# AtoVproject_16n_ALPS_V1_2NL.net
KiCad netlist of a schematic drawn in EAGLE
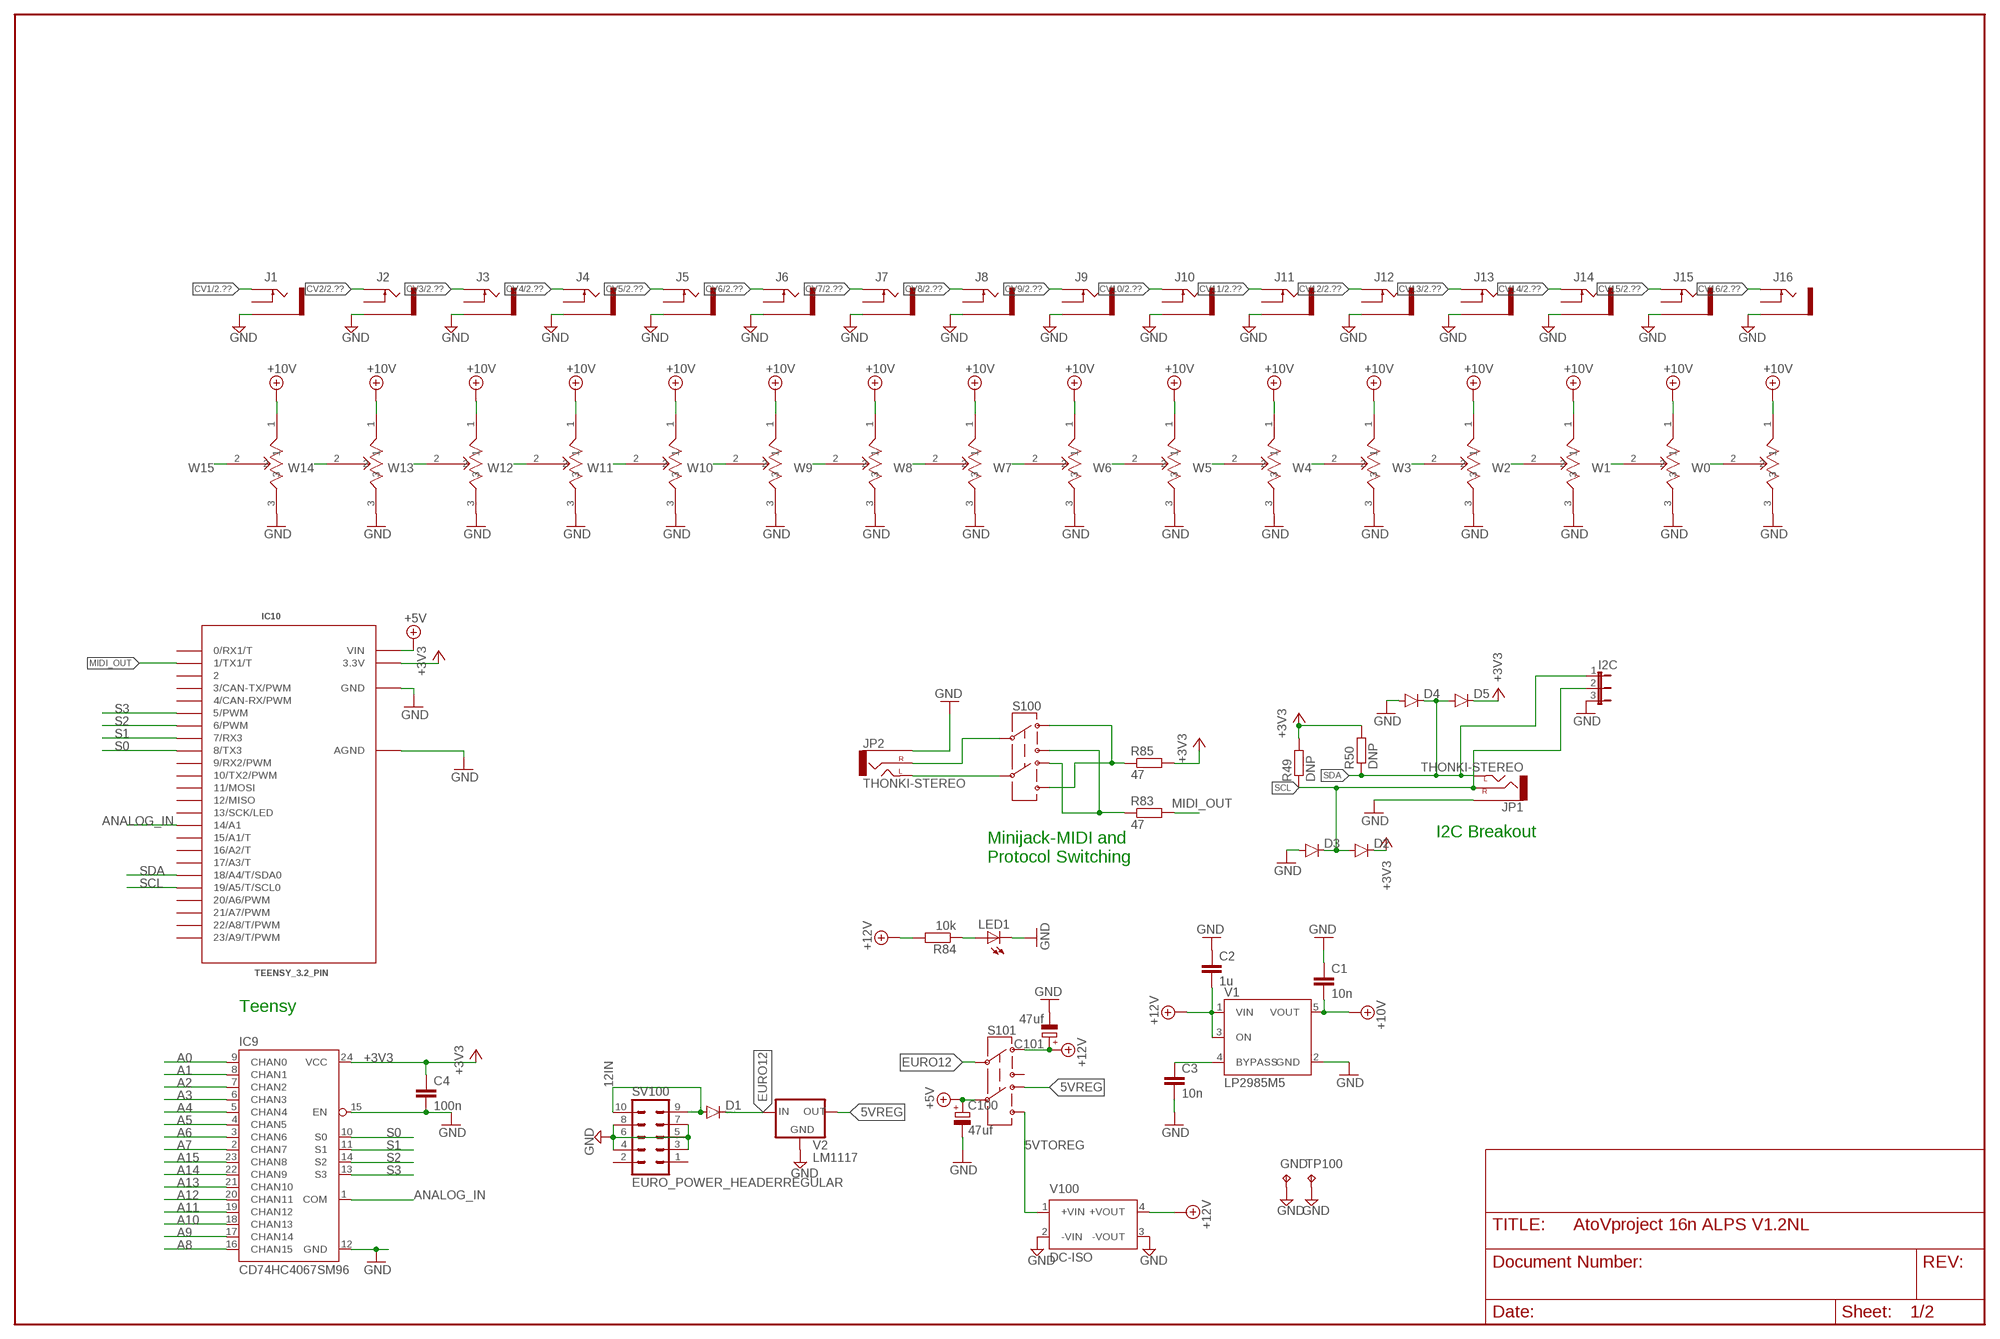
[diagram p0: schematic, sheet 1]
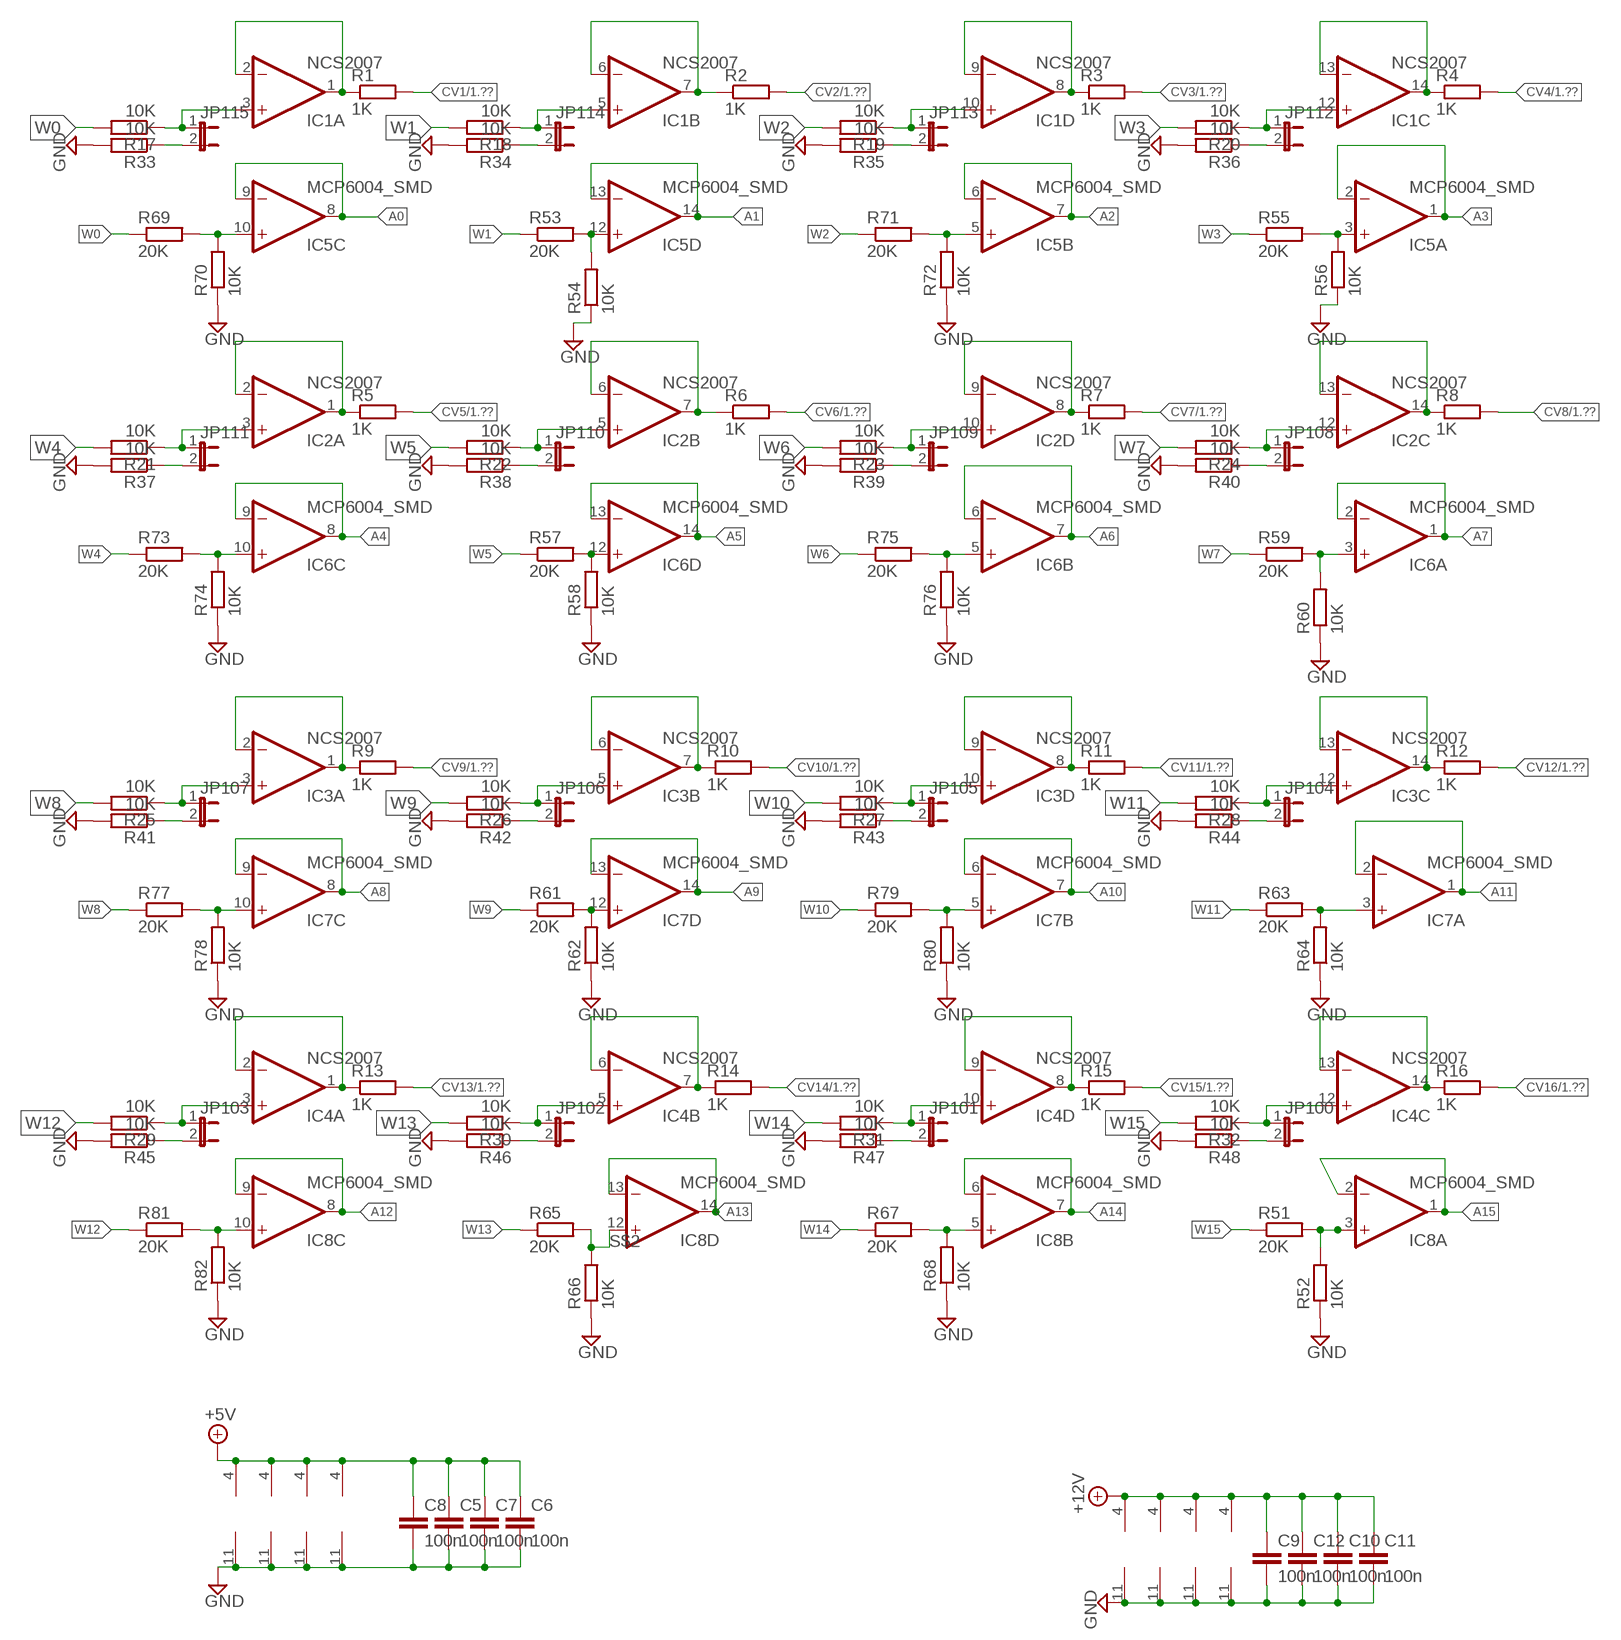
[diagram p1: schematic, sheet 2]

(export (version "E")
  (design (tool "Eeschema 10.0.6"))
  (components
    (comp (ref "C1")
      (value "10n")
      (footprint "eagle-import:C0805")
      (libsource (lib "eagle-import") (part "C-EUC0805"))
    )
    (comp (ref "C2")
      (value "1u")
      (footprint "eagle-import:C0805")
      (libsource (lib "eagle-import") (part "C-EUC0805"))
    )
    (comp (ref "C3")
      (value "10n")
      (footprint "eagle-import:C0805")
      (libsource (lib "eagle-import") (part "C-EUC0805"))
    )
    (comp (ref "C4")
      (value "100n")
      (footprint "eagle-import:C0805")
      (libsource (lib "eagle-import") (part "C-EUC0805"))
    )
    (comp (ref "C100")
      (value "47uf")
      (footprint "eagle-import:E2,5-6")
      (libsource (lib "eagle-import") (part "CPOL-EUE2.5-6"))
    )
    (comp (ref "C101")
      (value "47uf")
      (footprint "eagle-import:E2,5-6")
      (libsource (lib "eagle-import") (part "CPOL-EUE2.5-6"))
    )
    (comp (ref "D1")
      (value "DIODE-SOD123")
      (footprint "eagle-import:SOD123")
      (libsource (lib "eagle-import") (part "DIODE-SOD123"))
    )
    (comp (ref "D2")
      (value "DIODESOD123")
      (footprint "eagle-import:SOD-123")
      (libsource (lib "eagle-import") (part "DIODESOD123"))
    )
    (comp (ref "D3")
      (value "DIODESOD123")
      (footprint "eagle-import:SOD-123")
      (libsource (lib "eagle-import") (part "DIODESOD123"))
    )
    (comp (ref "D4")
      (value "DIODESOD123")
      (footprint "eagle-import:SOD-123")
      (libsource (lib "eagle-import") (part "DIODESOD123"))
    )
    (comp (ref "D5")
      (value "DIODESOD123")
      (footprint "eagle-import:SOD-123")
      (libsource (lib "eagle-import") (part "DIODESOD123"))
    )
    (comp (ref "GND")
      (value "TPPAD1-17")
      (footprint "eagle-import:P1-17")
      (libsource (lib "eagle-import") (part "TPPAD1-17"))
    )
    (comp (ref "I2C")
      (value "JP2E")
      (footprint "eagle-import:JP2")
      (libsource (lib "eagle-import") (part "JP2E"))
    )
    (comp (ref "IC9")
      (value "CD74HC4067SM96")
      (footprint "eagle-import:SOIC127P1030X265-24")
      (libsource (lib "eagle-import") (part "744067SO24"))
    )
    (comp (ref "IC10")
      (value "TEENSY_3.2_PIN")
      (footprint "eagle-import:TEENSY_3_AND_LC_SERIES_BOARDS_V1.4_TEENSY_3.0-3.2&LC_DIL")
      (libsource (lib "eagle-import") (part "TEENSY_3.2_PIN"))
    )
    (comp (ref "J1")
      (value "THONKICONN")
      (footprint "eagle-import:WQP-PJ301M-12JACK-BANANA")
      (libsource (lib "eagle-import") (part "THONKICONN"))
    )
    (comp (ref "J2")
      (value "THONKICONN")
      (footprint "eagle-import:WQP-PJ301M-12JACK-BANANA")
      (libsource (lib "eagle-import") (part "THONKICONN"))
    )
    (comp (ref "J3")
      (value "THONKICONN")
      (footprint "eagle-import:WQP-PJ301M-12JACK-BANANA")
      (libsource (lib "eagle-import") (part "THONKICONN"))
    )
    (comp (ref "J4")
      (value "THONKICONN")
      (footprint "eagle-import:WQP-PJ301M-12JACK-BANANA")
      (libsource (lib "eagle-import") (part "THONKICONN"))
    )
    (comp (ref "J5")
      (value "THONKICONN")
      (footprint "eagle-import:WQP-PJ301M-12JACK-BANANA")
      (libsource (lib "eagle-import") (part "THONKICONN"))
    )
    (comp (ref "J6")
      (value "THONKICONN")
      (footprint "eagle-import:WQP-PJ301M-12JACK-BANANA")
      (libsource (lib "eagle-import") (part "THONKICONN"))
    )
    (comp (ref "J7")
      (value "THONKICONN")
      (footprint "eagle-import:WQP-PJ301M-12JACK-BANANA")
      (libsource (lib "eagle-import") (part "THONKICONN"))
    )
    (comp (ref "J8")
      (value "THONKICONN")
      (footprint "eagle-import:WQP-PJ301M-12JACK-BANANA")
      (libsource (lib "eagle-import") (part "THONKICONN"))
    )
    (comp (ref "J9")
      (value "THONKICONN")
      (footprint "eagle-import:WQP-PJ301M-12JACK-BANANA")
      (libsource (lib "eagle-import") (part "THONKICONN"))
    )
    (comp (ref "J10")
      (value "THONKICONN")
      (footprint "eagle-import:WQP-PJ301M-12JACK-BANANA")
      (libsource (lib "eagle-import") (part "THONKICONN"))
    )
    (comp (ref "J11")
      (value "THONKICONN")
      (footprint "eagle-import:WQP-PJ301M-12JACK-BANANA")
      (libsource (lib "eagle-import") (part "THONKICONN"))
    )
    (comp (ref "J12")
      (value "THONKICONN")
      (footprint "eagle-import:WQP-PJ301M-12JACK-BANANA")
      (libsource (lib "eagle-import") (part "THONKICONN"))
    )
    (comp (ref "J13")
      (value "THONKICONN")
      (footprint "eagle-import:WQP-PJ301M-12JACK-BANANA")
      (libsource (lib "eagle-import") (part "THONKICONN"))
    )
    (comp (ref "J14")
      (value "THONKICONN")
      (footprint "eagle-import:WQP-PJ301M-12JACK-BANANA")
      (libsource (lib "eagle-import") (part "THONKICONN"))
    )
    (comp (ref "J15")
      (value "THONKICONN")
      (footprint "eagle-import:WQP-PJ301M-12JACK-BANANA")
      (libsource (lib "eagle-import") (part "THONKICONN"))
    )
    (comp (ref "J16")
      (value "THONKICONN")
      (footprint "eagle-import:WQP-PJ301M-12JACK-BANANA")
      (libsource (lib "eagle-import") (part "THONKICONN"))
    )
    (comp (ref "JP1")
      (value "THONKI-STEREO")
      (footprint "eagle-import:WQP-PJ366ST_JACK")
      (libsource (lib "eagle-import") (part "THONKI-STEREO"))
    )
    (comp (ref "JP2")
      (value "THONKI-STEREO")
      (footprint "eagle-import:WQP-PJ366ST_JACK")
      (libsource (lib "eagle-import") (part "THONKI-STEREO"))
    )
    (comp (ref "LED1")
      (value "LED")
      (footprint "eagle-import:LED3MM")
      (libsource (lib "eagle-import") (part "LED"))
    )
    (comp (ref "R49")
      (value "DNP")
      (footprint "eagle-import:R0805")
      (libsource (lib "eagle-import") (part "R-EU_R0805"))
    )
    (comp (ref "R50")
      (value "DNP")
      (footprint "eagle-import:R0805")
      (libsource (lib "eagle-import") (part "R-EU_R0805"))
    )
    (comp (ref "R83")
      (value "47")
      (footprint "eagle-import:R0805")
      (libsource (lib "eagle-import") (part "R-EU_R0805"))
    )
    (comp (ref "R84")
      (value "10k")
      (footprint "eagle-import:R0805")
      (libsource (lib "eagle-import") (part "R-EU_R0805"))
    )
    (comp (ref "R85")
      (value "47")
      (footprint "eagle-import:R0805")
      (libsource (lib "eagle-import") (part "R-EU_R0805"))
    )
    (comp (ref "S100")
      (value "SWITCH-DPDTEG2211")
      (footprint "eagle-import:EG2211")
      (libsource (lib "eagle-import") (part "SWITCH-DPDTEG2211"))
    )
    (comp (ref "S101")
      (value "SWITCH-DPDTEG2211")
      (footprint "eagle-import:EG2211")
      (libsource (lib "eagle-import") (part "SWITCH-DPDTEG2211"))
    )
    (comp (ref "SV100")
      (value "EURO_POWER_HEADERREGULAR")
      (footprint "eagle-import:EURO_POWER_HEADER")
      (libsource (lib "eagle-import") (part "EURO_POWER_HEADERREGULAR"))
    )
    (comp (ref "TP100")
      (value "TPPAD1-17")
      (footprint "eagle-import:P1-17")
      (libsource (lib "eagle-import") (part "TPPAD1-17"))
    )
    (comp (ref "U$1")
      (value "SLIDERSALPS-60MM")
      (footprint "eagle-import:MONOME_RS6011SP600")
      (libsource (lib "eagle-import") (part "SLIDERSALPS-60MM"))
    )
    (comp (ref "U$2")
      (value "SLIDERSALPS-60MM")
      (footprint "eagle-import:MONOME_RS6011SP600")
      (libsource (lib "eagle-import") (part "SLIDERSALPS-60MM"))
    )
    (comp (ref "U$3")
      (value "SLIDERSALPS-60MM")
      (footprint "eagle-import:MONOME_RS6011SP600")
      (libsource (lib "eagle-import") (part "SLIDERSALPS-60MM"))
    )
    (comp (ref "U$4")
      (value "SLIDERSALPS-60MM")
      (footprint "eagle-import:MONOME_RS6011SP600")
      (libsource (lib "eagle-import") (part "SLIDERSALPS-60MM"))
    )
    (comp (ref "U$5")
      (value "SLIDERSALPS-60MM")
      (footprint "eagle-import:MONOME_RS6011SP600")
      (libsource (lib "eagle-import") (part "SLIDERSALPS-60MM"))
    )
    (comp (ref "U$6")
      (value "SLIDERSALPS-60MM")
      (footprint "eagle-import:MONOME_RS6011SP600")
      (libsource (lib "eagle-import") (part "SLIDERSALPS-60MM"))
    )
    (comp (ref "U$7")
      (value "SLIDERSALPS-60MM")
      (footprint "eagle-import:MONOME_RS6011SP600")
      (libsource (lib "eagle-import") (part "SLIDERSALPS-60MM"))
    )
    (comp (ref "U$8")
      (value "SLIDERSALPS-60MM")
      (footprint "eagle-import:MONOME_RS6011SP600")
      (libsource (lib "eagle-import") (part "SLIDERSALPS-60MM"))
    )
    (comp (ref "U$9")
      (value "SLIDERSALPS-60MM")
      (footprint "eagle-import:MONOME_RS6011SP600")
      (libsource (lib "eagle-import") (part "SLIDERSALPS-60MM"))
    )
    (comp (ref "U$10")
      (value "SLIDERSALPS-60MM")
      (footprint "eagle-import:MONOME_RS6011SP600")
      (libsource (lib "eagle-import") (part "SLIDERSALPS-60MM"))
    )
    (comp (ref "U$11")
      (value "SLIDERSALPS-60MM")
      (footprint "eagle-import:MONOME_RS6011SP600")
      (libsource (lib "eagle-import") (part "SLIDERSALPS-60MM"))
    )
    (comp (ref "U$12")
      (value "SLIDERSALPS-60MM")
      (footprint "eagle-import:MONOME_RS6011SP600")
      (libsource (lib "eagle-import") (part "SLIDERSALPS-60MM"))
    )
    (comp (ref "U$13")
      (value "SLIDERSALPS-60MM")
      (footprint "eagle-import:MONOME_RS6011SP600")
      (libsource (lib "eagle-import") (part "SLIDERSALPS-60MM"))
    )
    (comp (ref "U$14")
      (value "SLIDERSALPS-60MM")
      (footprint "eagle-import:MONOME_RS6011SP600")
      (libsource (lib "eagle-import") (part "SLIDERSALPS-60MM"))
    )
    (comp (ref "U$15")
      (value "SLIDERSALPS-60MM")
      (footprint "eagle-import:MONOME_RS6011SP600")
      (libsource (lib "eagle-import") (part "SLIDERSALPS-60MM"))
    )
    (comp (ref "U$16")
      (value "SLIDERSALPS-60MM")
      (footprint "eagle-import:MONOME_RS6011SP600")
      (libsource (lib "eagle-import") (part "SLIDERSALPS-60MM"))
    )
    (comp (ref "V1")
      (value "LP2985M5")
      (footprint "eagle-import:SOT23-5")
      (libsource (lib "eagle-import") (part "LP2985M5"))
    )
    (comp (ref "V2")
      (value "LM1117")
      (footprint "eagle-import:SOT223")
      (libsource (lib "eagle-import") (part "LM1117"))
    )
    (comp (ref "V100")
      (value "DC-ISO")
      (footprint "eagle-import:TMA")
      (libsource (lib "eagle-import") (part "DC-ISO"))
    )
    (comp (ref "C5")
      (value "100n")
      (footprint "eagle-import:C0805")
      (libsource (lib "eagle-import") (part "C-EUC0805"))
    )
    (comp (ref "C6")
      (value "100n")
      (footprint "eagle-import:C0805")
      (libsource (lib "eagle-import") (part "C-EUC0805"))
    )
    (comp (ref "C7")
      (value "100n")
      (footprint "eagle-import:C0805")
      (libsource (lib "eagle-import") (part "C-EUC0805"))
    )
    (comp (ref "C8")
      (value "100n")
      (footprint "eagle-import:C0805")
      (libsource (lib "eagle-import") (part "C-EUC0805"))
    )
    (comp (ref "C9")
      (value "100n")
      (footprint "eagle-import:C0805")
      (libsource (lib "eagle-import") (part "C-EUC0805"))
    )
    (comp (ref "C10")
      (value "100n")
      (footprint "eagle-import:C0805")
      (libsource (lib "eagle-import") (part "C-EUC0805"))
    )
    (comp (ref "C11")
      (value "100n")
      (footprint "eagle-import:C0805")
      (libsource (lib "eagle-import") (part "C-EUC0805"))
    )
    (comp (ref "C12")
      (value "100n")
      (footprint "eagle-import:C0805")
      (libsource (lib "eagle-import") (part "C-EUC0805"))
    )
    (comp (ref "IC1")
      (value "NCS2007")
      (footprint "eagle-import:SO14")
      (libsource (lib "eagle-import") (part "TL074"))
    )
    (comp (ref "IC2")
      (value "NCS2007")
      (footprint "eagle-import:SO14")
      (libsource (lib "eagle-import") (part "TL074"))
    )
    (comp (ref "IC3")
      (value "NCS2007")
      (footprint "eagle-import:SO14")
      (libsource (lib "eagle-import") (part "TL074"))
    )
    (comp (ref "IC4")
      (value "NCS2007")
      (footprint "eagle-import:SO14")
      (libsource (lib "eagle-import") (part "TL074"))
    )
    (comp (ref "IC5")
      (value "MCP6004_SMD")
      (footprint "eagle-import:SO14")
      (libsource (lib "eagle-import") (part "MCP6004_SMD"))
    )
    (comp (ref "IC6")
      (value "MCP6004_SMD")
      (footprint "eagle-import:SO14")
      (libsource (lib "eagle-import") (part "MCP6004_SMD"))
    )
    (comp (ref "IC7")
      (value "MCP6004_SMD")
      (footprint "eagle-import:SO14")
      (libsource (lib "eagle-import") (part "MCP6004_SMD"))
    )
    (comp (ref "IC8")
      (value "MCP6004_SMD")
      (footprint "eagle-import:SO14")
      (libsource (lib "eagle-import") (part "MCP6004_SMD"))
    )
    (comp (ref "JP100")
      (value "JP1E3D")
      (footprint "eagle-import:1X02")
      (libsource (lib "eagle-import") (part "JP1E3D"))
    )
    (comp (ref "JP101")
      (value "JP1E3D")
      (footprint "eagle-import:1X02")
      (libsource (lib "eagle-import") (part "JP1E3D"))
    )
    (comp (ref "JP102")
      (value "JP1E3D")
      (footprint "eagle-import:1X02")
      (libsource (lib "eagle-import") (part "JP1E3D"))
    )
    (comp (ref "JP103")
      (value "JP1E3D")
      (footprint "eagle-import:1X02")
      (libsource (lib "eagle-import") (part "JP1E3D"))
    )
    (comp (ref "JP104")
      (value "JP1E3D")
      (footprint "eagle-import:1X02")
      (libsource (lib "eagle-import") (part "JP1E3D"))
    )
    (comp (ref "JP105")
      (value "JP1E3D")
      (footprint "eagle-import:1X02")
      (libsource (lib "eagle-import") (part "JP1E3D"))
    )
    (comp (ref "JP106")
      (value "JP1E3D")
      (footprint "eagle-import:1X02")
      (libsource (lib "eagle-import") (part "JP1E3D"))
    )
    (comp (ref "JP107")
      (value "JP1E3D")
      (footprint "eagle-import:1X02")
      (libsource (lib "eagle-import") (part "JP1E3D"))
    )
    (comp (ref "JP108")
      (value "JP1E3D")
      (footprint "eagle-import:1X02")
      (libsource (lib "eagle-import") (part "JP1E3D"))
    )
    (comp (ref "JP109")
      (value "JP1E3D")
      (footprint "eagle-import:1X02")
      (libsource (lib "eagle-import") (part "JP1E3D"))
    )
    (comp (ref "JP110")
      (value "JP1E3D")
      (footprint "eagle-import:1X02")
      (libsource (lib "eagle-import") (part "JP1E3D"))
    )
    (comp (ref "JP111")
      (value "JP1E3D")
      (footprint "eagle-import:1X02")
      (libsource (lib "eagle-import") (part "JP1E3D"))
    )
    (comp (ref "JP112")
      (value "JP1E3D")
      (footprint "eagle-import:1X02")
      (libsource (lib "eagle-import") (part "JP1E3D"))
    )
    (comp (ref "JP113")
      (value "JP1E3D")
      (footprint "eagle-import:1X02")
      (libsource (lib "eagle-import") (part "JP1E3D"))
    )
    (comp (ref "JP114")
      (value "JP1E3D")
      (footprint "eagle-import:1X02")
      (libsource (lib "eagle-import") (part "JP1E3D"))
    )
    (comp (ref "JP115")
      (value "JP1E3D")
      (footprint "eagle-import:1X02")
      (libsource (lib "eagle-import") (part "JP1E3D"))
    )
    (comp (ref "R1")
      (value "1K")
      (footprint "eagle-import:R0805")
      (libsource (lib "eagle-import") (part "R-EU_R0805"))
    )
    (comp (ref "R2")
      (value "1K")
      (footprint "eagle-import:R0805")
      (libsource (lib "eagle-import") (part "R-EU_R0805"))
    )
    (comp (ref "R3")
      (value "1K")
      (footprint "eagle-import:R0805")
      (libsource (lib "eagle-import") (part "R-EU_R0805"))
    )
    (comp (ref "R4")
      (value "1K")
      (footprint "eagle-import:R0805")
      (libsource (lib "eagle-import") (part "R-EU_R0805"))
    )
    (comp (ref "R5")
      (value "1K")
      (footprint "eagle-import:R0805")
      (libsource (lib "eagle-import") (part "R-EU_R0805"))
    )
    (comp (ref "R6")
      (value "1K")
      (footprint "eagle-import:R0805")
      (libsource (lib "eagle-import") (part "R-EU_R0805"))
    )
    (comp (ref "R7")
      (value "1K")
      (footprint "eagle-import:R0805")
      (libsource (lib "eagle-import") (part "R-EU_R0805"))
    )
    (comp (ref "R8")
      (value "1K")
      (footprint "eagle-import:R0805")
      (libsource (lib "eagle-import") (part "R-EU_R0805"))
    )
    (comp (ref "R9")
      (value "1K")
      (footprint "eagle-import:R0805")
      (libsource (lib "eagle-import") (part "R-EU_R0805"))
    )
    (comp (ref "R10")
      (value "1K")
      (footprint "eagle-import:R0805")
      (libsource (lib "eagle-import") (part "R-EU_R0805"))
    )
    (comp (ref "R11")
      (value "1K")
      (footprint "eagle-import:R0805")
      (libsource (lib "eagle-import") (part "R-EU_R0805"))
    )
    (comp (ref "R12")
      (value "1K")
      (footprint "eagle-import:R0805")
      (libsource (lib "eagle-import") (part "R-EU_R0805"))
    )
    (comp (ref "R13")
      (value "1K")
      (footprint "eagle-import:R0805")
      (libsource (lib "eagle-import") (part "R-EU_R0805"))
    )
    (comp (ref "R14")
      (value "1K")
      (footprint "eagle-import:R0805")
      (libsource (lib "eagle-import") (part "R-EU_R0805"))
    )
    (comp (ref "R15")
      (value "1K")
      (footprint "eagle-import:R0805")
      (libsource (lib "eagle-import") (part "R-EU_R0805"))
    )
    (comp (ref "R16")
      (value "1K")
      (footprint "eagle-import:R0805")
      (libsource (lib "eagle-import") (part "R-EU_R0805"))
    )
    (comp (ref "R17")
      (value "10K")
      (footprint "eagle-import:R0805")
      (libsource (lib "eagle-import") (part "R-EU_R0805"))
    )
    (comp (ref "R18")
      (value "10K")
      (footprint "eagle-import:R0805")
      (libsource (lib "eagle-import") (part "R-EU_R0805"))
    )
    (comp (ref "R19")
      (value "10K")
      (footprint "eagle-import:R0805")
      (libsource (lib "eagle-import") (part "R-EU_R0805"))
    )
    (comp (ref "R20")
      (value "10K")
      (footprint "eagle-import:R0805")
      (libsource (lib "eagle-import") (part "R-EU_R0805"))
    )
    (comp (ref "R21")
      (value "10K")
      (footprint "eagle-import:R0805")
      (libsource (lib "eagle-import") (part "R-EU_R0805"))
    )
    (comp (ref "R22")
      (value "10K")
      (footprint "eagle-import:R0805")
      (libsource (lib "eagle-import") (part "R-EU_R0805"))
    )
    (comp (ref "R23")
      (value "10K")
      (footprint "eagle-import:R0805")
      (libsource (lib "eagle-import") (part "R-EU_R0805"))
    )
    (comp (ref "R24")
      (value "10K")
      (footprint "eagle-import:R0805")
      (libsource (lib "eagle-import") (part "R-EU_R0805"))
    )
    (comp (ref "R25")
      (value "10K")
      (footprint "eagle-import:R0805")
      (libsource (lib "eagle-import") (part "R-EU_R0805"))
    )
    (comp (ref "R26")
      (value "10K")
      (footprint "eagle-import:R0805")
      (libsource (lib "eagle-import") (part "R-EU_R0805"))
    )
    (comp (ref "R27")
      (value "10K")
      (footprint "eagle-import:R0805")
      (libsource (lib "eagle-import") (part "R-EU_R0805"))
    )
    (comp (ref "R28")
      (value "10K")
      (footprint "eagle-import:R0805")
      (libsource (lib "eagle-import") (part "R-EU_R0805"))
    )
    (comp (ref "R29")
      (value "10K")
      (footprint "eagle-import:R0805")
      (libsource (lib "eagle-import") (part "R-EU_R0805"))
    )
    (comp (ref "R30")
      (value "10K")
      (footprint "eagle-import:R0805")
      (libsource (lib "eagle-import") (part "R-EU_R0805"))
    )
    (comp (ref "R31")
      (value "10K")
      (footprint "eagle-import:R0805")
      (libsource (lib "eagle-import") (part "R-EU_R0805"))
    )
    (comp (ref "R32")
      (value "10K")
      (footprint "eagle-import:R0805")
      (libsource (lib "eagle-import") (part "R-EU_R0805"))
    )
    (comp (ref "R33")
      (value "10K")
      (footprint "eagle-import:R0805")
      (libsource (lib "eagle-import") (part "R-EU_R0805"))
    )
    (comp (ref "R34")
      (value "10K")
      (footprint "eagle-import:R0805")
      (libsource (lib "eagle-import") (part "R-EU_R0805"))
    )
    (comp (ref "R35")
      (value "10K")
      (footprint "eagle-import:R0805")
      (libsource (lib "eagle-import") (part "R-EU_R0805"))
    )
    (comp (ref "R36")
      (value "10K")
      (footprint "eagle-import:R0805")
      (libsource (lib "eagle-import") (part "R-EU_R0805"))
    )
    (comp (ref "R37")
      (value "10K")
      (footprint "eagle-import:R0805")
      (libsource (lib "eagle-import") (part "R-EU_R0805"))
    )
    (comp (ref "R38")
      (value "10K")
      (footprint "eagle-import:R0805")
      (libsource (lib "eagle-import") (part "R-EU_R0805"))
    )
    (comp (ref "R39")
      (value "10K")
      (footprint "eagle-import:R0805")
      (libsource (lib "eagle-import") (part "R-EU_R0805"))
    )
    (comp (ref "R40")
      (value "10K")
      (footprint "eagle-import:R0805")
      (libsource (lib "eagle-import") (part "R-EU_R0805"))
    )
    (comp (ref "R41")
      (value "10K")
      (footprint "eagle-import:R0805")
      (libsource (lib "eagle-import") (part "R-EU_R0805"))
    )
    (comp (ref "R42")
      (value "10K")
      (footprint "eagle-import:R0805")
      (libsource (lib "eagle-import") (part "R-EU_R0805"))
    )
    (comp (ref "R43")
      (value "10K")
      (footprint "eagle-import:R0805")
      (libsource (lib "eagle-import") (part "R-EU_R0805"))
    )
    (comp (ref "R44")
      (value "10K")
      (footprint "eagle-import:R0805")
      (libsource (lib "eagle-import") (part "R-EU_R0805"))
    )
    (comp (ref "R45")
      (value "10K")
      (footprint "eagle-import:R0805")
      (libsource (lib "eagle-import") (part "R-EU_R0805"))
    )
    (comp (ref "R46")
      (value "10K")
      (footprint "eagle-import:R0805")
      (libsource (lib "eagle-import") (part "R-EU_R0805"))
    )
    (comp (ref "R47")
      (value "10K")
      (footprint "eagle-import:R0805")
      (libsource (lib "eagle-import") (part "R-EU_R0805"))
    )
    (comp (ref "R48")
      (value "10K")
      (footprint "eagle-import:R0805")
      (libsource (lib "eagle-import") (part "R-EU_R0805"))
    )
    (comp (ref "R51")
      (value "20K")
      (footprint "eagle-import:R0805")
      (libsource (lib "eagle-import") (part "R-EU_R0805"))
    )
    (comp (ref "R52")
      (value "10K")
      (footprint "eagle-import:R0805")
      (libsource (lib "eagle-import") (part "R-EU_R0805"))
    )
    (comp (ref "R53")
      (value "20K")
      (footprint "eagle-import:R0805")
      (libsource (lib "eagle-import") (part "R-EU_R0805"))
    )
    (comp (ref "R54")
      (value "10K")
      (footprint "eagle-import:R0805")
      (libsource (lib "eagle-import") (part "R-EU_R0805"))
    )
    (comp (ref "R55")
      (value "20K")
      (footprint "eagle-import:R0805")
      (libsource (lib "eagle-import") (part "R-EU_R0805"))
    )
    (comp (ref "R56")
      (value "10K")
      (footprint "eagle-import:R0805")
      (libsource (lib "eagle-import") (part "R-EU_R0805"))
    )
    (comp (ref "R57")
      (value "20K")
      (footprint "eagle-import:R0805")
      (libsource (lib "eagle-import") (part "R-EU_R0805"))
    )
    (comp (ref "R58")
      (value "10K")
      (footprint "eagle-import:R0805")
      (libsource (lib "eagle-import") (part "R-EU_R0805"))
    )
    (comp (ref "R59")
      (value "20K")
      (footprint "eagle-import:R0805")
      (libsource (lib "eagle-import") (part "R-EU_R0805"))
    )
    (comp (ref "R60")
      (value "10K")
      (footprint "eagle-import:R0805")
      (libsource (lib "eagle-import") (part "R-EU_R0805"))
    )
    (comp (ref "R61")
      (value "20K")
      (footprint "eagle-import:R0805")
      (libsource (lib "eagle-import") (part "R-EU_R0805"))
    )
    (comp (ref "R62")
      (value "10K")
      (footprint "eagle-import:R0805")
      (libsource (lib "eagle-import") (part "R-EU_R0805"))
    )
    (comp (ref "R63")
      (value "20K")
      (footprint "eagle-import:R0805")
      (libsource (lib "eagle-import") (part "R-EU_R0805"))
    )
    (comp (ref "R64")
      (value "10K")
      (footprint "eagle-import:R0805")
      (libsource (lib "eagle-import") (part "R-EU_R0805"))
    )
    (comp (ref "R65")
      (value "20K")
      (footprint "eagle-import:R0805")
      (libsource (lib "eagle-import") (part "R-EU_R0805"))
    )
    (comp (ref "R66")
      (value "10K")
      (footprint "eagle-import:R0805")
      (libsource (lib "eagle-import") (part "R-EU_R0805"))
    )
    (comp (ref "R67")
      (value "20K")
      (footprint "eagle-import:R0805")
      (libsource (lib "eagle-import") (part "R-EU_R0805"))
    )
    (comp (ref "R68")
      (value "10K")
      (footprint "eagle-import:R0805")
      (libsource (lib "eagle-import") (part "R-EU_R0805"))
    )
    (comp (ref "R69")
      (value "20K")
      (footprint "eagle-import:R0805")
      (libsource (lib "eagle-import") (part "R-EU_R0805"))
    )
    (comp (ref "R70")
      (value "10K")
      (footprint "eagle-import:R0805")
      (libsource (lib "eagle-import") (part "R-EU_R0805"))
    )
    (comp (ref "R71")
      (value "20K")
      (footprint "eagle-import:R0805")
      (libsource (lib "eagle-import") (part "R-EU_R0805"))
    )
    (comp (ref "R72")
      (value "10K")
      (footprint "eagle-import:R0805")
      (libsource (lib "eagle-import") (part "R-EU_R0805"))
    )
    (comp (ref "R73")
      (value "20K")
      (footprint "eagle-import:R0805")
      (libsource (lib "eagle-import") (part "R-EU_R0805"))
    )
    (comp (ref "R74")
      (value "10K")
      (footprint "eagle-import:R0805")
      (libsource (lib "eagle-import") (part "R-EU_R0805"))
    )
    (comp (ref "R75")
      (value "20K")
      (footprint "eagle-import:R0805")
      (libsource (lib "eagle-import") (part "R-EU_R0805"))
    )
    (comp (ref "R76")
      (value "10K")
      (footprint "eagle-import:R0805")
      (libsource (lib "eagle-import") (part "R-EU_R0805"))
    )
    (comp (ref "R77")
      (value "20K")
      (footprint "eagle-import:R0805")
      (libsource (lib "eagle-import") (part "R-EU_R0805"))
    )
    (comp (ref "R78")
      (value "10K")
      (footprint "eagle-import:R0805")
      (libsource (lib "eagle-import") (part "R-EU_R0805"))
    )
    (comp (ref "R79")
      (value "20K")
      (footprint "eagle-import:R0805")
      (libsource (lib "eagle-import") (part "R-EU_R0805"))
    )
    (comp (ref "R80")
      (value "10K")
      (footprint "eagle-import:R0805")
      (libsource (lib "eagle-import") (part "R-EU_R0805"))
    )
    (comp (ref "R81")
      (value "20K")
      (footprint "eagle-import:R0805")
      (libsource (lib "eagle-import") (part "R-EU_R0805"))
    )
    (comp (ref "R82")
      (value "10K")
      (footprint "eagle-import:R0805")
      (libsource (lib "eagle-import") (part "R-EU_R0805"))
    )
  )
  (nets
    (net (code "1") (name "+3V3") (class "Default")
      (node (ref "C4") (pin "1") (pinfunction "1_1") (pintype "passive"))
      (node (ref "D2") (pin "C") (pinfunction "C_C") (pintype "passive"))
      (node (ref "D5") (pin "C") (pinfunction "C_C") (pintype "passive"))
      (node (ref "IC10") (pin "3.3V") (pinfunction "3.3V_3.3V") (pintype "power_in"))
      (node (ref "IC9") (pin "24") (pinfunction "VCC_24") (pintype "bidirectional"))
      (node (ref "R49") (pin "2") (pinfunction "2_2") (pintype "passive"))
      (node (ref "R50") (pin "2") (pinfunction "2_2") (pintype "passive"))
      (node (ref "R85") (pin "2") (pinfunction "2_2") (pintype "passive"))
    )
    (net (code "2") (name "+5V") (class "Default")
      (node (ref "C100") (pin "+") (pinfunction "+_+") (pintype "passive"))
      (node (ref "C5") (pin "1") (pinfunction "1_1") (pintype "passive"))
      (node (ref "C6") (pin "1") (pinfunction "1_1") (pintype "passive"))
      (node (ref "C7") (pin "1") (pinfunction "1_1") (pintype "passive"))
      (node (ref "C8") (pin "1") (pinfunction "1_1") (pintype "passive"))
      (node (ref "IC10") (pin "VIN") (pinfunction "VIN_VIN") (pintype "power_in"))
      (node (ref "IC5") (pin "4") (pinfunction "V+_4") (pintype "power_in"))
      (node (ref "IC6") (pin "4") (pinfunction "V+_4") (pintype "power_in"))
      (node (ref "IC7") (pin "4") (pinfunction "V+_4") (pintype "power_in"))
      (node (ref "IC8") (pin "4") (pinfunction "V+_4") (pintype "power_in"))
      (node (ref "S101") (pin "P2") (pinfunction "5_P2") (pintype "bidirectional"))
    )
    (net (code "3") (name "+10V") (class "Default")
      (node (ref "C1") (pin "2") (pinfunction "2_2") (pintype "passive"))
      (node (ref "U$1") (pin "1") (pinfunction "1_1") (pintype "bidirectional"))
      (node (ref "U$10") (pin "1") (pinfunction "1_1") (pintype "bidirectional"))
      (node (ref "U$11") (pin "1") (pinfunction "1_1") (pintype "bidirectional"))
      (node (ref "U$12") (pin "1") (pinfunction "1_1") (pintype "bidirectional"))
      (node (ref "U$13") (pin "1") (pinfunction "1_1") (pintype "bidirectional"))
      (node (ref "U$14") (pin "1") (pinfunction "1_1") (pintype "bidirectional"))
      (node (ref "U$15") (pin "1") (pinfunction "1_1") (pintype "bidirectional"))
      (node (ref "U$16") (pin "1") (pinfunction "1_1") (pintype "bidirectional"))
      (node (ref "U$2") (pin "1") (pinfunction "1_1") (pintype "bidirectional"))
      (node (ref "U$3") (pin "1") (pinfunction "1_1") (pintype "bidirectional"))
      (node (ref "U$4") (pin "1") (pinfunction "1_1") (pintype "bidirectional"))
      (node (ref "U$5") (pin "1") (pinfunction "1_1") (pintype "bidirectional"))
      (node (ref "U$6") (pin "1") (pinfunction "1_1") (pintype "bidirectional"))
      (node (ref "U$7") (pin "1") (pinfunction "1_1") (pintype "bidirectional"))
      (node (ref "U$8") (pin "1") (pinfunction "1_1") (pintype "bidirectional"))
      (node (ref "U$9") (pin "1") (pinfunction "1_1") (pintype "bidirectional"))
      (node (ref "V1") (pin "5") (pinfunction "VOUT_5") (pintype "output"))
    )
    (net (code "4") (name "+12V") (class "Default")
      (node (ref "C10") (pin "1") (pinfunction "1_1") (pintype "passive"))
      (node (ref "C101") (pin "+") (pinfunction "+_+") (pintype "passive"))
      (node (ref "C11") (pin "1") (pinfunction "1_1") (pintype "passive"))
      (node (ref "C12") (pin "1") (pinfunction "1_1") (pintype "passive"))
      (node (ref "C2") (pin "2") (pinfunction "2_2") (pintype "passive"))
      (node (ref "C9") (pin "1") (pinfunction "1_1") (pintype "passive"))
      (node (ref "IC1") (pin "4") (pinfunction "V+_4") (pintype "power_in"))
      (node (ref "IC2") (pin "4") (pinfunction "V+_4") (pintype "power_in"))
      (node (ref "IC3") (pin "4") (pinfunction "V+_4") (pintype "power_in"))
      (node (ref "IC4") (pin "4") (pinfunction "V+_4") (pintype "power_in"))
      (node (ref "R84") (pin "2") (pinfunction "2_2") (pintype "passive"))
      (node (ref "S101") (pin "P1-TA") (pinfunction "1_P1-TA") (pintype "bidirectional"))
      (node (ref "V1") (pin "1") (pinfunction "VIN_1") (pintype "power_in"))
      (node (ref "V1") (pin "3") (pinfunction "ON_3") (pintype "input"))
      (node (ref "V100") (pin "4") (pinfunction "+VOUT_4") (pintype "passive"))
    )
    (net (code "5") (name "5VREG") (class "Default")
      (node (ref "S101") (pin "P2-TA") (pinfunction "4_P2-TA") (pintype "bidirectional"))
      (node (ref "V2") (pin "OUT") (pinfunction "OUT_OUT") (pintype "passive"))
      (node (ref "V2") (pin "TAB") (pinfunction "OUT_TAB") (pintype "passive"))
    )
    (net (code "6") (name "5VTOREG") (class "Default")
      (node (ref "S101") (pin "P2-TB") (pinfunction "6_P2-TB") (pintype "bidirectional"))
      (node (ref "V100") (pin "1") (pinfunction "+VIN_1") (pintype "passive"))
    )
    (net (code "7") (name "12IN") (class "Default")
      (node (ref "D1") (pin "A") (pinfunction "A_A") (pintype "passive"))
      (node (ref "SV100") (pin "10") (pinfunction "10_10") (pintype "passive"))
      (node (ref "SV100") (pin "9") (pinfunction "9_9") (pintype "passive"))
    )
    (net (code "8") (name "A0") (class "Default")
      (node (ref "IC5") (pin "8") (pinfunction "OUT_8") (pintype "output"))
      (node (ref "IC5") (pin "9") (pinfunction "-IN_9") (pintype "input"))
      (node (ref "IC9") (pin "9") (pinfunction "CHAN0_9") (pintype "bidirectional"))
    )
    (net (code "9") (name "A1") (class "Default")
      (node (ref "IC5") (pin "13") (pinfunction "-IN_13") (pintype "input"))
      (node (ref "IC5") (pin "14") (pinfunction "OUT_14") (pintype "output"))
      (node (ref "IC9") (pin "8") (pinfunction "CHAN1_8") (pintype "bidirectional"))
    )
    (net (code "10") (name "A2") (class "Default")
      (node (ref "IC5") (pin "6") (pinfunction "-IN_6") (pintype "input"))
      (node (ref "IC5") (pin "7") (pinfunction "OUT_7") (pintype "output"))
      (node (ref "IC9") (pin "7") (pinfunction "CHAN2_7") (pintype "bidirectional"))
    )
    (net (code "11") (name "A3") (class "Default")
      (node (ref "IC5") (pin "1") (pinfunction "OUT_1") (pintype "output"))
      (node (ref "IC5") (pin "2") (pinfunction "-IN_2") (pintype "input"))
      (node (ref "IC9") (pin "6") (pinfunction "CHAN3_6") (pintype "bidirectional"))
    )
    (net (code "12") (name "A4") (class "Default")
      (node (ref "IC6") (pin "8") (pinfunction "OUT_8") (pintype "output"))
      (node (ref "IC6") (pin "9") (pinfunction "-IN_9") (pintype "input"))
      (node (ref "IC9") (pin "5") (pinfunction "CHAN4_5") (pintype "bidirectional"))
    )
    (net (code "13") (name "A5") (class "Default")
      (node (ref "IC6") (pin "13") (pinfunction "-IN_13") (pintype "input"))
      (node (ref "IC6") (pin "14") (pinfunction "OUT_14") (pintype "output"))
      (node (ref "IC9") (pin "4") (pinfunction "CHAN5_4") (pintype "bidirectional"))
    )
    (net (code "14") (name "A6") (class "Default")
      (node (ref "IC6") (pin "6") (pinfunction "-IN_6") (pintype "input"))
      (node (ref "IC6") (pin "7") (pinfunction "OUT_7") (pintype "output"))
      (node (ref "IC9") (pin "3") (pinfunction "CHAN6_3") (pintype "bidirectional"))
    )
    (net (code "15") (name "A7") (class "Default")
      (node (ref "IC6") (pin "1") (pinfunction "OUT_1") (pintype "output"))
      (node (ref "IC6") (pin "2") (pinfunction "-IN_2") (pintype "input"))
      (node (ref "IC9") (pin "2") (pinfunction "CHAN7_2") (pintype "bidirectional"))
    )
    (net (code "16") (name "A8") (class "Default")
      (node (ref "IC7") (pin "8") (pinfunction "OUT_8") (pintype "output"))
      (node (ref "IC7") (pin "9") (pinfunction "-IN_9") (pintype "input"))
      (node (ref "IC9") (pin "16") (pinfunction "CHAN15_16") (pintype "bidirectional"))
    )
    (net (code "17") (name "A9") (class "Default")
      (node (ref "IC7") (pin "13") (pinfunction "-IN_13") (pintype "input"))
      (node (ref "IC7") (pin "14") (pinfunction "OUT_14") (pintype "output"))
      (node (ref "IC9") (pin "17") (pinfunction "CHAN14_17") (pintype "bidirectional"))
    )
    (net (code "18") (name "A10") (class "Default")
      (node (ref "IC7") (pin "6") (pinfunction "-IN_6") (pintype "input"))
      (node (ref "IC7") (pin "7") (pinfunction "OUT_7") (pintype "output"))
      (node (ref "IC9") (pin "18") (pinfunction "CHAN13_18") (pintype "bidirectional"))
    )
    (net (code "19") (name "A11") (class "Default")
      (node (ref "IC7") (pin "1") (pinfunction "OUT_1") (pintype "output"))
      (node (ref "IC7") (pin "2") (pinfunction "-IN_2") (pintype "input"))
      (node (ref "IC9") (pin "19") (pinfunction "CHAN12_19") (pintype "bidirectional"))
    )
    (net (code "20") (name "A12") (class "Default")
      (node (ref "IC8") (pin "8") (pinfunction "OUT_8") (pintype "output"))
      (node (ref "IC8") (pin "9") (pinfunction "-IN_9") (pintype "input"))
      (node (ref "IC9") (pin "20") (pinfunction "CHAN11_20") (pintype "bidirectional"))
    )
    (net (code "21") (name "A13") (class "Default")
      (node (ref "IC8") (pin "13") (pinfunction "-IN_13") (pintype "input"))
      (node (ref "IC8") (pin "14") (pinfunction "OUT_14") (pintype "output"))
      (node (ref "IC9") (pin "21") (pinfunction "CHAN10_21") (pintype "bidirectional"))
    )
    (net (code "22") (name "A14") (class "Default")
      (node (ref "IC8") (pin "6") (pinfunction "-IN_6") (pintype "input"))
      (node (ref "IC8") (pin "7") (pinfunction "OUT_7") (pintype "output"))
      (node (ref "IC9") (pin "22") (pinfunction "CHAN9_22") (pintype "bidirectional"))
    )
    (net (code "23") (name "A15") (class "Default")
      (node (ref "IC8") (pin "1") (pinfunction "OUT_1") (pintype "output"))
      (node (ref "IC8") (pin "2") (pinfunction "-IN_2") (pintype "input"))
      (node (ref "IC9") (pin "23") (pinfunction "CHAN8_23") (pintype "bidirectional"))
    )
    (net (code "24") (name "ANALOG_IN") (class "Default")
      (node (ref "IC10") (pin "14/A0") (pinfunction "14/A1_14/A0") (pintype "bidirectional"))
      (node (ref "IC9") (pin "1") (pinfunction "COM_1") (pintype "bidirectional"))
    )
    (net (code "25") (name "CV1") (class "Default")
      (node (ref "J1") (pin "P$1_TIP") (pinfunction "TIP_P$1_TIP") (pintype "passive"))
      (node (ref "R1") (pin "2") (pinfunction "2_2") (pintype "passive"))
    )
    (net (code "26") (name "CV2") (class "Default")
      (node (ref "J2") (pin "P$1_TIP") (pinfunction "TIP_P$1_TIP") (pintype "passive"))
      (node (ref "R2") (pin "2") (pinfunction "2_2") (pintype "passive"))
    )
    (net (code "27") (name "CV3") (class "Default")
      (node (ref "J3") (pin "P$1_TIP") (pinfunction "TIP_P$1_TIP") (pintype "passive"))
      (node (ref "R3") (pin "2") (pinfunction "2_2") (pintype "passive"))
    )
    (net (code "28") (name "CV4") (class "Default")
      (node (ref "J4") (pin "P$1_TIP") (pinfunction "TIP_P$1_TIP") (pintype "passive"))
      (node (ref "R4") (pin "2") (pinfunction "2_2") (pintype "passive"))
    )
    (net (code "29") (name "CV5") (class "Default")
      (node (ref "J5") (pin "P$1_TIP") (pinfunction "TIP_P$1_TIP") (pintype "passive"))
      (node (ref "R5") (pin "2") (pinfunction "2_2") (pintype "passive"))
    )
    (net (code "30") (name "CV6") (class "Default")
      (node (ref "J6") (pin "P$1_TIP") (pinfunction "TIP_P$1_TIP") (pintype "passive"))
      (node (ref "R6") (pin "2") (pinfunction "2_2") (pintype "passive"))
    )
    (net (code "31") (name "CV7") (class "Default")
      (node (ref "J7") (pin "P$1_TIP") (pinfunction "TIP_P$1_TIP") (pintype "passive"))
      (node (ref "R7") (pin "2") (pinfunction "2_2") (pintype "passive"))
    )
    (net (code "32") (name "CV8") (class "Default")
      (node (ref "J8") (pin "P$1_TIP") (pinfunction "TIP_P$1_TIP") (pintype "passive"))
      (node (ref "R8") (pin "2") (pinfunction "2_2") (pintype "passive"))
    )
    (net (code "33") (name "CV9") (class "Default")
      (node (ref "J9") (pin "P$1_TIP") (pinfunction "TIP_P$1_TIP") (pintype "passive"))
      (node (ref "R9") (pin "2") (pinfunction "2_2") (pintype "passive"))
    )
    (net (code "34") (name "CV10") (class "Default")
      (node (ref "J10") (pin "P$1_TIP") (pinfunction "TIP_P$1_TIP") (pintype "passive"))
      (node (ref "R10") (pin "2") (pinfunction "2_2") (pintype "passive"))
    )
    (net (code "35") (name "CV11") (class "Default")
      (node (ref "J11") (pin "P$1_TIP") (pinfunction "TIP_P$1_TIP") (pintype "passive"))
      (node (ref "R11") (pin "2") (pinfunction "2_2") (pintype "passive"))
    )
    (net (code "36") (name "CV12") (class "Default")
      (node (ref "J12") (pin "P$1_TIP") (pinfunction "TIP_P$1_TIP") (pintype "passive"))
      (node (ref "R12") (pin "2") (pinfunction "2_2") (pintype "passive"))
    )
    (net (code "37") (name "CV13") (class "Default")
      (node (ref "J13") (pin "P$1_TIP") (pinfunction "TIP_P$1_TIP") (pintype "passive"))
      (node (ref "R13") (pin "2") (pinfunction "2_2") (pintype "passive"))
    )
    (net (code "38") (name "CV14") (class "Default")
      (node (ref "J14") (pin "P$1_TIP") (pinfunction "TIP_P$1_TIP") (pintype "passive"))
      (node (ref "R14") (pin "2") (pinfunction "2_2") (pintype "passive"))
    )
    (net (code "39") (name "CV15") (class "Default")
      (node (ref "J15") (pin "P$1_TIP") (pinfunction "TIP_P$1_TIP") (pintype "passive"))
      (node (ref "R15") (pin "2") (pinfunction "2_2") (pintype "passive"))
    )
    (net (code "40") (name "CV16") (class "Default")
      (node (ref "J16") (pin "P$1_TIP") (pinfunction "TIP_P$1_TIP") (pintype "passive"))
      (node (ref "R16") (pin "2") (pinfunction "2_2") (pintype "passive"))
    )
    (net (code "41") (name "EURO12") (class "Default")
      (node (ref "D1") (pin "C") (pinfunction "C_C") (pintype "passive"))
      (node (ref "S101") (pin "P1") (pinfunction "2_P1") (pintype "bidirectional"))
      (node (ref "V2") (pin "IN") (pinfunction "IN_IN") (pintype "input"))
    )
    (net (code "42") (name "GND") (class "Default")
      (node (ref "C1") (pin "1") (pinfunction "1_1") (pintype "passive"))
      (node (ref "C10") (pin "2") (pinfunction "2_2") (pintype "passive"))
      (node (ref "C100") (pin "-") (pinfunction "-_-") (pintype "passive"))
      (node (ref "C101") (pin "-") (pinfunction "-_-") (pintype "passive"))
      (node (ref "C11") (pin "2") (pinfunction "2_2") (pintype "passive"))
      (node (ref "C12") (pin "2") (pinfunction "2_2") (pintype "passive"))
      (node (ref "C2") (pin "1") (pinfunction "1_1") (pintype "passive"))
      (node (ref "C3") (pin "2") (pinfunction "2_2") (pintype "passive"))
      (node (ref "C4") (pin "2") (pinfunction "2_2") (pintype "passive"))
      (node (ref "C5") (pin "2") (pinfunction "2_2") (pintype "passive"))
      (node (ref "C6") (pin "2") (pinfunction "2_2") (pintype "passive"))
      (node (ref "C7") (pin "2") (pinfunction "2_2") (pintype "passive"))
      (node (ref "C8") (pin "2") (pinfunction "2_2") (pintype "passive"))
      (node (ref "C9") (pin "2") (pinfunction "2_2") (pintype "passive"))
      (node (ref "D3") (pin "A") (pinfunction "A_A") (pintype "passive"))
      (node (ref "D4") (pin "A") (pinfunction "A_A") (pintype "passive"))
      (node (ref "GND") (pin "TP") (pinfunction "TP_TP") (pintype "input"))
      (node (ref "I2C") (pin "3") (pinfunction "3_3") (pintype "passive"))
      (node (ref "IC1") (pin "11") (pinfunction "V-_11") (pintype "power_in"))
      (node (ref "IC10") (pin "AGND") (pinfunction "AGND_AGND") (pintype "power_in"))
      (node (ref "IC10") (pin "GND") (pinfunction "GND_GND") (pintype "power_in"))
      (node (ref "IC2") (pin "11") (pinfunction "V-_11") (pintype "power_in"))
      (node (ref "IC3") (pin "11") (pinfunction "V-_11") (pintype "power_in"))
      (node (ref "IC4") (pin "11") (pinfunction "V-_11") (pintype "power_in"))
      (node (ref "IC5") (pin "11") (pinfunction "V-_11") (pintype "power_in"))
      (node (ref "IC6") (pin "11") (pinfunction "V-_11") (pintype "power_in"))
      (node (ref "IC7") (pin "11") (pinfunction "V-_11") (pintype "power_in"))
      (node (ref "IC8") (pin "11") (pinfunction "V-_11") (pintype "power_in"))
      (node (ref "IC9") (pin "12") (pinfunction "GND_12") (pintype "bidirectional"))
      (node (ref "IC9") (pin "15") (pinfunction "EN_15") (pintype "input"))
      (node (ref "J1") (pin "P$3_SLEEVE") (pinfunction "SLEEVE_P$3_SLEEVE") (pintype "passive"))
      (node (ref "J10") (pin "P$3_SLEEVE") (pinfunction "SLEEVE_P$3_SLEEVE") (pintype "passive"))
      (node (ref "J11") (pin "P$3_SLEEVE") (pinfunction "SLEEVE_P$3_SLEEVE") (pintype "passive"))
      (node (ref "J12") (pin "P$3_SLEEVE") (pinfunction "SLEEVE_P$3_SLEEVE") (pintype "passive"))
      (node (ref "J13") (pin "P$3_SLEEVE") (pinfunction "SLEEVE_P$3_SLEEVE") (pintype "passive"))
      (node (ref "J14") (pin "P$3_SLEEVE") (pinfunction "SLEEVE_P$3_SLEEVE") (pintype "passive"))
      (node (ref "J15") (pin "P$3_SLEEVE") (pinfunction "SLEEVE_P$3_SLEEVE") (pintype "passive"))
      (node (ref "J16") (pin "P$3_SLEEVE") (pinfunction "SLEEVE_P$3_SLEEVE") (pintype "passive"))
      (node (ref "J2") (pin "P$3_SLEEVE") (pinfunction "SLEEVE_P$3_SLEEVE") (pintype "passive"))
      (node (ref "J3") (pin "P$3_SLEEVE") (pinfunction "SLEEVE_P$3_SLEEVE") (pintype "passive"))
      (node (ref "J4") (pin "P$3_SLEEVE") (pinfunction "SLEEVE_P$3_SLEEVE") (pintype "passive"))
      (node (ref "J5") (pin "P$3_SLEEVE") (pinfunction "SLEEVE_P$3_SLEEVE") (pintype "passive"))
      (node (ref "J6") (pin "P$3_SLEEVE") (pinfunction "SLEEVE_P$3_SLEEVE") (pintype "passive"))
      (node (ref "J7") (pin "P$3_SLEEVE") (pinfunction "SLEEVE_P$3_SLEEVE") (pintype "passive"))
      (node (ref "J8") (pin "P$3_SLEEVE") (pinfunction "SLEEVE_P$3_SLEEVE") (pintype "passive"))
      (node (ref "J9") (pin "P$3_SLEEVE") (pinfunction "SLEEVE_P$3_SLEEVE") (pintype "passive"))
      (node (ref "JP1") (pin "P$3_SLEEVE") (pinfunction "SLEEVE_P$3_SLEEVE") (pintype "bidirectional"))
      (node (ref "JP2") (pin "P$3_SLEEVE") (pinfunction "SLEEVE_P$3_SLEEVE") (pintype "bidirectional"))
      (node (ref "LED1") (pin "K") (pinfunction "C_K") (pintype "passive"))
      (node (ref "R33") (pin "2") (pinfunction "2_2") (pintype "passive"))
      (node (ref "R34") (pin "2") (pinfunction "2_2") (pintype "passive"))
      (node (ref "R35") (pin "2") (pinfunction "2_2") (pintype "passive"))
      (node (ref "R36") (pin "2") (pinfunction "2_2") (pintype "passive"))
      (node (ref "R37") (pin "2") (pinfunction "2_2") (pintype "passive"))
      (node (ref "R38") (pin "2") (pinfunction "2_2") (pintype "passive"))
      (node (ref "R39") (pin "2") (pinfunction "2_2") (pintype "passive"))
      (node (ref "R40") (pin "2") (pinfunction "2_2") (pintype "passive"))
      (node (ref "R41") (pin "2") (pinfunction "2_2") (pintype "passive"))
      (node (ref "R42") (pin "2") (pinfunction "2_2") (pintype "passive"))
      (node (ref "R43") (pin "2") (pinfunction "2_2") (pintype "passive"))
      (node (ref "R44") (pin "2") (pinfunction "2_2") (pintype "passive"))
      (node (ref "R45") (pin "2") (pinfunction "2_2") (pintype "passive"))
      (node (ref "R46") (pin "2") (pinfunction "2_2") (pintype "passive"))
      (node (ref "R47") (pin "2") (pinfunction "2_2") (pintype "passive"))
      (node (ref "R48") (pin "2") (pinfunction "2_2") (pintype "passive"))
      (node (ref "R52") (pin "1") (pinfunction "1_1") (pintype "passive"))
      (node (ref "R54") (pin "1") (pinfunction "1_1") (pintype "passive"))
      (node (ref "R56") (pin "1") (pinfunction "1_1") (pintype "passive"))
      (node (ref "R58") (pin "1") (pinfunction "1_1") (pintype "passive"))
      (node (ref "R60") (pin "1") (pinfunction "1_1") (pintype "passive"))
      (node (ref "R62") (pin "1") (pinfunction "1_1") (pintype "passive"))
      (node (ref "R64") (pin "1") (pinfunction "1_1") (pintype "passive"))
      (node (ref "R66") (pin "1") (pinfunction "1_1") (pintype "passive"))
      (node (ref "R68") (pin "1") (pinfunction "1_1") (pintype "passive"))
      (node (ref "R70") (pin "1") (pinfunction "1_1") (pintype "passive"))
      (node (ref "R72") (pin "1") (pinfunction "1_1") (pintype "passive"))
      (node (ref "R74") (pin "1") (pinfunction "1_1") (pintype "passive"))
      (node (ref "R76") (pin "1") (pinfunction "1_1") (pintype "passive"))
      (node (ref "R78") (pin "1") (pinfunction "1_1") (pintype "passive"))
      (node (ref "R80") (pin "1") (pinfunction "1_1") (pintype "passive"))
      (node (ref "R82") (pin "1") (pinfunction "1_1") (pintype "passive"))
      (node (ref "SV100") (pin "3") (pinfunction "3_3") (pintype "passive"))
      (node (ref "SV100") (pin "4") (pinfunction "4_4") (pintype "passive"))
      (node (ref "SV100") (pin "5") (pinfunction "5_5") (pintype "passive"))
      (node (ref "SV100") (pin "6") (pinfunction "6_6") (pintype "passive"))
      (node (ref "SV100") (pin "7") (pinfunction "7_7") (pintype "passive"))
      (node (ref "SV100") (pin "8") (pinfunction "8_8") (pintype "passive"))
      (node (ref "TP100") (pin "TP") (pinfunction "TP_TP") (pintype "input"))
      (node (ref "U$1") (pin "3") (pinfunction "3_3") (pintype "bidirectional"))
      (node (ref "U$10") (pin "3") (pinfunction "3_3") (pintype "bidirectional"))
      (node (ref "U$11") (pin "3") (pinfunction "3_3") (pintype "bidirectional"))
      (node (ref "U$12") (pin "3") (pinfunction "3_3") (pintype "bidirectional"))
      (node (ref "U$13") (pin "3") (pinfunction "3_3") (pintype "bidirectional"))
      (node (ref "U$14") (pin "3") (pinfunction "3_3") (pintype "bidirectional"))
      (node (ref "U$15") (pin "3") (pinfunction "3_3") (pintype "bidirectional"))
      (node (ref "U$16") (pin "3") (pinfunction "3_3") (pintype "bidirectional"))
      (node (ref "U$2") (pin "3") (pinfunction "3_3") (pintype "bidirectional"))
      (node (ref "U$3") (pin "3") (pinfunction "3_3") (pintype "bidirectional"))
      (node (ref "U$4") (pin "3") (pinfunction "3_3") (pintype "bidirectional"))
      (node (ref "U$5") (pin "3") (pinfunction "3_3") (pintype "bidirectional"))
      (node (ref "U$6") (pin "3") (pinfunction "3_3") (pintype "bidirectional"))
      (node (ref "U$7") (pin "3") (pinfunction "3_3") (pintype "bidirectional"))
      (node (ref "U$8") (pin "3") (pinfunction "3_3") (pintype "bidirectional"))
      (node (ref "U$9") (pin "3") (pinfunction "3_3") (pintype "bidirectional"))
      (node (ref "V1") (pin "2") (pinfunction "GND_2") (pintype "power_in"))
      (node (ref "V100") (pin "2") (pinfunction "-VIN_2") (pintype "passive"))
      (node (ref "V100") (pin "3") (pinfunction "-VOUT_3") (pintype "passive"))
      (node (ref "V2") (pin "GND") (pinfunction "GND_GND") (pintype "input"))
    )
    (net (code "43") (name "MIDI_OUT") (class "Default")
      (node (ref "IC10") (pin "1") (pinfunction "1/TX1/T_1") (pintype "bidirectional"))
      (node (ref "R83") (pin "2") (pinfunction "2_2") (pintype "passive"))
    )
    (net (code "44") (name "Net-(IC1A-+IN)") (class "Default")
      (node (ref "IC1") (pin "3") (pinfunction "+IN_3") (pintype "input"))
      (node (ref "JP115") (pin "1") (pinfunction "1_1") (pintype "passive"))
      (node (ref "R17") (pin "1") (pinfunction "1_1") (pintype "passive"))
    )
    (net (code "45") (name "Net-(IC1A--IN)") (class "Default")
      (node (ref "IC1") (pin "1") (pinfunction "OUT_1") (pintype "output"))
      (node (ref "IC1") (pin "2") (pinfunction "-IN_2") (pintype "input"))
      (node (ref "R1") (pin "1") (pinfunction "1_1") (pintype "passive"))
    )
    (net (code "46") (name "Net-(IC1B-+IN)") (class "Default")
      (node (ref "IC1") (pin "5") (pinfunction "+IN_5") (pintype "input"))
      (node (ref "JP114") (pin "1") (pinfunction "1_1") (pintype "passive"))
      (node (ref "R18") (pin "1") (pinfunction "1_1") (pintype "passive"))
    )
    (net (code "47") (name "Net-(IC1B--IN)") (class "Default")
      (node (ref "IC1") (pin "6") (pinfunction "-IN_6") (pintype "input"))
      (node (ref "IC1") (pin "7") (pinfunction "OUT_7") (pintype "output"))
      (node (ref "R2") (pin "1") (pinfunction "1_1") (pintype "passive"))
    )
    (net (code "48") (name "Net-(IC1C-+IN)") (class "Default")
      (node (ref "IC1") (pin "12") (pinfunction "+IN_12") (pintype "input"))
      (node (ref "JP112") (pin "1") (pinfunction "1_1") (pintype "passive"))
      (node (ref "R20") (pin "1") (pinfunction "1_1") (pintype "passive"))
    )
    (net (code "49") (name "Net-(IC1C--IN)") (class "Default")
      (node (ref "IC1") (pin "13") (pinfunction "-IN_13") (pintype "input"))
      (node (ref "IC1") (pin "14") (pinfunction "OUT_14") (pintype "output"))
      (node (ref "R4") (pin "1") (pinfunction "1_1") (pintype "passive"))
    )
    (net (code "50") (name "Net-(IC1D-+IN)") (class "Default")
      (node (ref "IC1") (pin "10") (pinfunction "+IN_10") (pintype "input"))
      (node (ref "JP113") (pin "1") (pinfunction "1_1") (pintype "passive"))
      (node (ref "R19") (pin "1") (pinfunction "1_1") (pintype "passive"))
    )
    (net (code "51") (name "Net-(IC1D--IN)") (class "Default")
      (node (ref "IC1") (pin "8") (pinfunction "OUT_8") (pintype "output"))
      (node (ref "IC1") (pin "9") (pinfunction "-IN_9") (pintype "input"))
      (node (ref "R3") (pin "1") (pinfunction "1_1") (pintype "passive"))
    )
    (net (code "52") (name "Net-(IC2A-+IN)") (class "Default")
      (node (ref "IC2") (pin "3") (pinfunction "+IN_3") (pintype "input"))
      (node (ref "JP111") (pin "1") (pinfunction "1_1") (pintype "passive"))
      (node (ref "R21") (pin "1") (pinfunction "1_1") (pintype "passive"))
    )
    (net (code "53") (name "Net-(IC2A--IN)") (class "Default")
      (node (ref "IC2") (pin "1") (pinfunction "OUT_1") (pintype "output"))
      (node (ref "IC2") (pin "2") (pinfunction "-IN_2") (pintype "input"))
      (node (ref "R5") (pin "1") (pinfunction "1_1") (pintype "passive"))
    )
    (net (code "54") (name "Net-(IC2B-+IN)") (class "Default")
      (node (ref "IC2") (pin "5") (pinfunction "+IN_5") (pintype "input"))
      (node (ref "JP110") (pin "1") (pinfunction "1_1") (pintype "passive"))
      (node (ref "R22") (pin "1") (pinfunction "1_1") (pintype "passive"))
    )
    (net (code "55") (name "Net-(IC2B--IN)") (class "Default")
      (node (ref "IC2") (pin "6") (pinfunction "-IN_6") (pintype "input"))
      (node (ref "IC2") (pin "7") (pinfunction "OUT_7") (pintype "output"))
      (node (ref "R6") (pin "1") (pinfunction "1_1") (pintype "passive"))
    )
    (net (code "56") (name "Net-(IC2C-+IN)") (class "Default")
      (node (ref "IC2") (pin "12") (pinfunction "+IN_12") (pintype "input"))
      (node (ref "JP108") (pin "1") (pinfunction "1_1") (pintype "passive"))
      (node (ref "R24") (pin "1") (pinfunction "1_1") (pintype "passive"))
    )
    (net (code "57") (name "Net-(IC2C--IN)") (class "Default")
      (node (ref "IC2") (pin "13") (pinfunction "-IN_13") (pintype "input"))
      (node (ref "IC2") (pin "14") (pinfunction "OUT_14") (pintype "output"))
      (node (ref "R8") (pin "1") (pinfunction "1_1") (pintype "passive"))
    )
    (net (code "58") (name "Net-(IC2D-+IN)") (class "Default")
      (node (ref "IC2") (pin "10") (pinfunction "+IN_10") (pintype "input"))
      (node (ref "JP109") (pin "1") (pinfunction "1_1") (pintype "passive"))
      (node (ref "R23") (pin "1") (pinfunction "1_1") (pintype "passive"))
    )
    (net (code "59") (name "Net-(IC2D--IN)") (class "Default")
      (node (ref "IC2") (pin "8") (pinfunction "OUT_8") (pintype "output"))
      (node (ref "IC2") (pin "9") (pinfunction "-IN_9") (pintype "input"))
      (node (ref "R7") (pin "1") (pinfunction "1_1") (pintype "passive"))
    )
    (net (code "60") (name "Net-(IC3A-+IN)") (class "Default")
      (node (ref "IC3") (pin "3") (pinfunction "+IN_3") (pintype "input"))
      (node (ref "JP107") (pin "1") (pinfunction "1_1") (pintype "passive"))
      (node (ref "R25") (pin "1") (pinfunction "1_1") (pintype "passive"))
    )
    (net (code "61") (name "Net-(IC3A--IN)") (class "Default")
      (node (ref "IC3") (pin "1") (pinfunction "OUT_1") (pintype "output"))
      (node (ref "IC3") (pin "2") (pinfunction "-IN_2") (pintype "input"))
      (node (ref "R9") (pin "1") (pinfunction "1_1") (pintype "passive"))
    )
    (net (code "62") (name "Net-(IC3B-+IN)") (class "Default")
      (node (ref "IC3") (pin "5") (pinfunction "+IN_5") (pintype "input"))
      (node (ref "JP106") (pin "1") (pinfunction "1_1") (pintype "passive"))
      (node (ref "R26") (pin "1") (pinfunction "1_1") (pintype "passive"))
    )
    (net (code "63") (name "Net-(IC3B--IN)") (class "Default")
      (node (ref "IC3") (pin "6") (pinfunction "-IN_6") (pintype "input"))
      (node (ref "IC3") (pin "7") (pinfunction "OUT_7") (pintype "output"))
      (node (ref "R10") (pin "1") (pinfunction "1_1") (pintype "passive"))
    )
    (net (code "64") (name "Net-(IC3C-+IN)") (class "Default")
      (node (ref "IC3") (pin "12") (pinfunction "+IN_12") (pintype "input"))
      (node (ref "JP104") (pin "1") (pinfunction "1_1") (pintype "passive"))
      (node (ref "R28") (pin "1") (pinfunction "1_1") (pintype "passive"))
    )
    (net (code "65") (name "Net-(IC3C--IN)") (class "Default")
      (node (ref "IC3") (pin "13") (pinfunction "-IN_13") (pintype "input"))
      (node (ref "IC3") (pin "14") (pinfunction "OUT_14") (pintype "output"))
      (node (ref "R12") (pin "1") (pinfunction "1_1") (pintype "passive"))
    )
    (net (code "66") (name "Net-(IC3D-+IN)") (class "Default")
      (node (ref "IC3") (pin "10") (pinfunction "+IN_10") (pintype "input"))
      (node (ref "JP105") (pin "1") (pinfunction "1_1") (pintype "passive"))
      (node (ref "R27") (pin "1") (pinfunction "1_1") (pintype "passive"))
    )
    (net (code "67") (name "Net-(IC3D--IN)") (class "Default")
      (node (ref "IC3") (pin "8") (pinfunction "OUT_8") (pintype "output"))
      (node (ref "IC3") (pin "9") (pinfunction "-IN_9") (pintype "input"))
      (node (ref "R11") (pin "1") (pinfunction "1_1") (pintype "passive"))
    )
    (net (code "68") (name "Net-(IC4A-+IN)") (class "Default")
      (node (ref "IC4") (pin "3") (pinfunction "+IN_3") (pintype "input"))
      (node (ref "JP103") (pin "1") (pinfunction "1_1") (pintype "passive"))
      (node (ref "R29") (pin "1") (pinfunction "1_1") (pintype "passive"))
    )
    (net (code "69") (name "Net-(IC4A--IN)") (class "Default")
      (node (ref "IC4") (pin "1") (pinfunction "OUT_1") (pintype "output"))
      (node (ref "IC4") (pin "2") (pinfunction "-IN_2") (pintype "input"))
      (node (ref "R13") (pin "1") (pinfunction "1_1") (pintype "passive"))
    )
    (net (code "70") (name "Net-(IC4B-+IN)") (class "Default")
      (node (ref "IC4") (pin "5") (pinfunction "+IN_5") (pintype "input"))
      (node (ref "JP102") (pin "1") (pinfunction "1_1") (pintype "passive"))
      (node (ref "R30") (pin "1") (pinfunction "1_1") (pintype "passive"))
    )
    (net (code "71") (name "Net-(IC4B--IN)") (class "Default")
      (node (ref "IC4") (pin "6") (pinfunction "-IN_6") (pintype "input"))
      (node (ref "IC4") (pin "7") (pinfunction "OUT_7") (pintype "output"))
      (node (ref "R14") (pin "1") (pinfunction "1_1") (pintype "passive"))
    )
    (net (code "72") (name "Net-(IC4C-+IN)") (class "Default")
      (node (ref "IC4") (pin "12") (pinfunction "+IN_12") (pintype "input"))
      (node (ref "JP100") (pin "1") (pinfunction "1_1") (pintype "passive"))
      (node (ref "R32") (pin "1") (pinfunction "1_1") (pintype "passive"))
    )
    (net (code "73") (name "Net-(IC4C--IN)") (class "Default")
      (node (ref "IC4") (pin "13") (pinfunction "-IN_13") (pintype "input"))
      (node (ref "IC4") (pin "14") (pinfunction "OUT_14") (pintype "output"))
      (node (ref "R16") (pin "1") (pinfunction "1_1") (pintype "passive"))
    )
    (net (code "74") (name "Net-(IC4D-+IN)") (class "Default")
      (node (ref "IC4") (pin "10") (pinfunction "+IN_10") (pintype "input"))
      (node (ref "JP101") (pin "1") (pinfunction "1_1") (pintype "passive"))
      (node (ref "R31") (pin "1") (pinfunction "1_1") (pintype "passive"))
    )
    (net (code "75") (name "Net-(IC4D--IN)") (class "Default")
      (node (ref "IC4") (pin "8") (pinfunction "OUT_8") (pintype "output"))
      (node (ref "IC4") (pin "9") (pinfunction "-IN_9") (pintype "input"))
      (node (ref "R15") (pin "1") (pinfunction "1_1") (pintype "passive"))
    )
    (net (code "76") (name "Net-(IC5A-+IN)") (class "Default")
      (node (ref "IC5") (pin "3") (pinfunction "+IN_3") (pintype "input"))
      (node (ref "R55") (pin "2") (pinfunction "2_2") (pintype "passive"))
      (node (ref "R56") (pin "2") (pinfunction "2_2") (pintype "passive"))
    )
    (net (code "77") (name "Net-(IC5B-+IN)") (class "Default")
      (node (ref "IC5") (pin "5") (pinfunction "+IN_5") (pintype "input"))
      (node (ref "R71") (pin "2") (pinfunction "2_2") (pintype "passive"))
      (node (ref "R72") (pin "2") (pinfunction "2_2") (pintype "passive"))
    )
    (net (code "78") (name "Net-(IC5C-+IN)") (class "Default")
      (node (ref "IC5") (pin "10") (pinfunction "+IN_10") (pintype "input"))
      (node (ref "R69") (pin "2") (pinfunction "2_2") (pintype "passive"))
      (node (ref "R70") (pin "2") (pinfunction "2_2") (pintype "passive"))
    )
    (net (code "79") (name "Net-(IC5D-+IN)") (class "Default")
      (node (ref "IC5") (pin "12") (pinfunction "+IN_12") (pintype "input"))
      (node (ref "R53") (pin "2") (pinfunction "2_2") (pintype "passive"))
      (node (ref "R54") (pin "2") (pinfunction "2_2") (pintype "passive"))
    )
    (net (code "80") (name "Net-(IC6A-+IN)") (class "Default")
      (node (ref "IC6") (pin "3") (pinfunction "+IN_3") (pintype "input"))
      (node (ref "R59") (pin "2") (pinfunction "2_2") (pintype "passive"))
      (node (ref "R60") (pin "2") (pinfunction "2_2") (pintype "passive"))
    )
    (net (code "81") (name "Net-(IC6B-+IN)") (class "Default")
      (node (ref "IC6") (pin "5") (pinfunction "+IN_5") (pintype "input"))
      (node (ref "R75") (pin "2") (pinfunction "2_2") (pintype "passive"))
      (node (ref "R76") (pin "2") (pinfunction "2_2") (pintype "passive"))
    )
    (net (code "82") (name "Net-(IC6C-+IN)") (class "Default")
      (node (ref "IC6") (pin "10") (pinfunction "+IN_10") (pintype "input"))
      (node (ref "R73") (pin "2") (pinfunction "2_2") (pintype "passive"))
      (node (ref "R74") (pin "2") (pinfunction "2_2") (pintype "passive"))
    )
    (net (code "83") (name "Net-(IC6D-+IN)") (class "Default")
      (node (ref "IC6") (pin "12") (pinfunction "+IN_12") (pintype "input"))
      (node (ref "R57") (pin "2") (pinfunction "2_2") (pintype "passive"))
      (node (ref "R58") (pin "2") (pinfunction "2_2") (pintype "passive"))
    )
    (net (code "84") (name "Net-(IC7A-+IN)") (class "Default")
      (node (ref "IC7") (pin "3") (pinfunction "+IN_3") (pintype "input"))
      (node (ref "R63") (pin "2") (pinfunction "2_2") (pintype "passive"))
      (node (ref "R64") (pin "2") (pinfunction "2_2") (pintype "passive"))
    )
    (net (code "85") (name "Net-(IC7B-+IN)") (class "Default")
      (node (ref "IC7") (pin "5") (pinfunction "+IN_5") (pintype "input"))
      (node (ref "R79") (pin "2") (pinfunction "2_2") (pintype "passive"))
      (node (ref "R80") (pin "2") (pinfunction "2_2") (pintype "passive"))
    )
    (net (code "86") (name "Net-(IC7C-+IN)") (class "Default")
      (node (ref "IC7") (pin "10") (pinfunction "+IN_10") (pintype "input"))
      (node (ref "R77") (pin "2") (pinfunction "2_2") (pintype "passive"))
      (node (ref "R78") (pin "2") (pinfunction "2_2") (pintype "passive"))
    )
    (net (code "87") (name "Net-(IC7D-+IN)") (class "Default")
      (node (ref "IC7") (pin "12") (pinfunction "+IN_12") (pintype "input"))
      (node (ref "R61") (pin "2") (pinfunction "2_2") (pintype "passive"))
      (node (ref "R62") (pin "2") (pinfunction "2_2") (pintype "passive"))
    )
    (net (code "88") (name "Net-(IC8A-+IN)") (class "Default")
      (node (ref "IC8") (pin "3") (pinfunction "+IN_3") (pintype "input"))
      (node (ref "R51") (pin "2") (pinfunction "2_2") (pintype "passive"))
      (node (ref "R52") (pin "2") (pinfunction "2_2") (pintype "passive"))
    )
    (net (code "89") (name "Net-(IC8B-+IN)") (class "Default")
      (node (ref "IC8") (pin "5") (pinfunction "+IN_5") (pintype "input"))
      (node (ref "R67") (pin "2") (pinfunction "2_2") (pintype "passive"))
      (node (ref "R68") (pin "2") (pinfunction "2_2") (pintype "passive"))
    )
    (net (code "90") (name "Net-(IC8C-+IN)") (class "Default")
      (node (ref "IC8") (pin "10") (pinfunction "+IN_10") (pintype "input"))
      (node (ref "R81") (pin "2") (pinfunction "2_2") (pintype "passive"))
      (node (ref "R82") (pin "2") (pinfunction "2_2") (pintype "passive"))
    )
    (net (code "91") (name "Net-(JP2-LEFT)") (class "Default")
      (node (ref "JP2") (pin "P$1_TIP") (pinfunction "LEFT_P$1_TIP") (pintype "bidirectional"))
      (node (ref "S100") (pin "P2") (pinfunction "5_P2") (pintype "bidirectional"))
    )
    (net (code "92") (name "Net-(JP2-RIGHT)") (class "Default")
      (node (ref "JP2") (pin "P$2_SWITCH") (pinfunction "RIGHT_P$2_SWITCH") (pintype "bidirectional"))
      (node (ref "S100") (pin "P1") (pinfunction "2_P1") (pintype "bidirectional"))
    )
    (net (code "93") (name "Net-(JP100-Pad2)") (class "Default")
      (node (ref "JP100") (pin "2") (pinfunction "2_2") (pintype "passive"))
      (node (ref "R48") (pin "1") (pinfunction "1_1") (pintype "passive"))
    )
    (net (code "94") (name "Net-(JP101-Pad2)") (class "Default")
      (node (ref "JP101") (pin "2") (pinfunction "2_2") (pintype "passive"))
      (node (ref "R47") (pin "1") (pinfunction "1_1") (pintype "passive"))
    )
    (net (code "95") (name "Net-(JP102-Pad2)") (class "Default")
      (node (ref "JP102") (pin "2") (pinfunction "2_2") (pintype "passive"))
      (node (ref "R46") (pin "1") (pinfunction "1_1") (pintype "passive"))
    )
    (net (code "96") (name "Net-(JP103-Pad2)") (class "Default")
      (node (ref "JP103") (pin "2") (pinfunction "2_2") (pintype "passive"))
      (node (ref "R45") (pin "1") (pinfunction "1_1") (pintype "passive"))
    )
    (net (code "97") (name "Net-(JP104-Pad2)") (class "Default")
      (node (ref "JP104") (pin "2") (pinfunction "2_2") (pintype "passive"))
      (node (ref "R44") (pin "1") (pinfunction "1_1") (pintype "passive"))
    )
    (net (code "98") (name "Net-(JP105-Pad2)") (class "Default")
      (node (ref "JP105") (pin "2") (pinfunction "2_2") (pintype "passive"))
      (node (ref "R43") (pin "1") (pinfunction "1_1") (pintype "passive"))
    )
    (net (code "99") (name "Net-(JP106-Pad2)") (class "Default")
      (node (ref "JP106") (pin "2") (pinfunction "2_2") (pintype "passive"))
      (node (ref "R42") (pin "1") (pinfunction "1_1") (pintype "passive"))
    )
    (net (code "100") (name "Net-(JP107-Pad2)") (class "Default")
      (node (ref "JP107") (pin "2") (pinfunction "2_2") (pintype "passive"))
      (node (ref "R41") (pin "1") (pinfunction "1_1") (pintype "passive"))
    )
    (net (code "101") (name "Net-(JP108-Pad2)") (class "Default")
      (node (ref "JP108") (pin "2") (pinfunction "2_2") (pintype "passive"))
      (node (ref "R40") (pin "1") (pinfunction "1_1") (pintype "passive"))
    )
    (net (code "102") (name "Net-(JP109-Pad2)") (class "Default")
      (node (ref "JP109") (pin "2") (pinfunction "2_2") (pintype "passive"))
      (node (ref "R39") (pin "1") (pinfunction "1_1") (pintype "passive"))
    )
    (net (code "103") (name "Net-(JP110-Pad2)") (class "Default")
      (node (ref "JP110") (pin "2") (pinfunction "2_2") (pintype "passive"))
      (node (ref "R38") (pin "1") (pinfunction "1_1") (pintype "passive"))
    )
    (net (code "104") (name "Net-(JP111-Pad2)") (class "Default")
      (node (ref "JP111") (pin "2") (pinfunction "2_2") (pintype "passive"))
      (node (ref "R37") (pin "1") (pinfunction "1_1") (pintype "passive"))
    )
    (net (code "105") (name "Net-(JP112-Pad2)") (class "Default")
      (node (ref "JP112") (pin "2") (pinfunction "2_2") (pintype "passive"))
      (node (ref "R36") (pin "1") (pinfunction "1_1") (pintype "passive"))
    )
    (net (code "106") (name "Net-(JP113-Pad2)") (class "Default")
      (node (ref "JP113") (pin "2") (pinfunction "2_2") (pintype "passive"))
      (node (ref "R35") (pin "1") (pinfunction "1_1") (pintype "passive"))
    )
    (net (code "107") (name "Net-(JP114-Pad2)") (class "Default")
      (node (ref "JP114") (pin "2") (pinfunction "2_2") (pintype "passive"))
      (node (ref "R34") (pin "1") (pinfunction "1_1") (pintype "passive"))
    )
    (net (code "108") (name "Net-(JP115-Pad2)") (class "Default")
      (node (ref "JP115") (pin "2") (pinfunction "2_2") (pintype "passive"))
      (node (ref "R33") (pin "1") (pinfunction "1_1") (pintype "passive"))
    )
    (net (code "109") (name "Net-(LED1-PadA)") (class "Default")
      (node (ref "LED1") (pin "A") (pinfunction "A_A") (pintype "passive"))
      (node (ref "R84") (pin "1") (pinfunction "1_1") (pintype "passive"))
    )
    (net (code "110") (name "Net-(S100-1)") (class "Default")
      (node (ref "R85") (pin "1") (pinfunction "1_1") (pintype "passive"))
      (node (ref "S100") (pin "P1-TA") (pinfunction "1_P1-TA") (pintype "bidirectional"))
      (node (ref "S100") (pin "P2-TB") (pinfunction "6_P2-TB") (pintype "bidirectional"))
    )
    (net (code "111") (name "Net-(S100-3)") (class "Default")
      (node (ref "R83") (pin "1") (pinfunction "1_1") (pintype "passive"))
      (node (ref "S100") (pin "P1-TB") (pinfunction "3_P1-TB") (pintype "bidirectional"))
      (node (ref "S100") (pin "P2-TA") (pinfunction "4_P2-TA") (pintype "bidirectional"))
    )
    (net (code "112") (name "Net-(V1-BYPASS)") (class "Default")
      (node (ref "C3") (pin "1") (pinfunction "1_1") (pintype "passive"))
      (node (ref "V1") (pin "4") (pinfunction "BYPASS_4") (pintype "passive"))
    )
    (net (code "113") (name "S$2") (class "Default")
      (node (ref "IC8") (pin "12") (pinfunction "+IN_12") (pintype "input"))
      (node (ref "R65") (pin "2") (pinfunction "2_2") (pintype "passive"))
      (node (ref "R66") (pin "2") (pinfunction "2_2") (pintype "passive"))
    )
    (net (code "114") (name "S0") (class "Default")
      (node (ref "IC10") (pin "8") (pinfunction "8/TX3_8") (pintype "bidirectional"))
      (node (ref "IC9") (pin "10") (pinfunction "S0_10") (pintype "input"))
    )
    (net (code "115") (name "S1") (class "Default")
      (node (ref "IC10") (pin "7") (pinfunction "7/RX3_7") (pintype "bidirectional"))
      (node (ref "IC9") (pin "11") (pinfunction "S1_11") (pintype "input"))
    )
    (net (code "116") (name "S2") (class "Default")
      (node (ref "IC10") (pin "6") (pinfunction "6/PWM_6") (pintype "bidirectional"))
      (node (ref "IC9") (pin "14") (pinfunction "S2_14") (pintype "input"))
    )
    (net (code "117") (name "S3") (class "Default")
      (node (ref "IC10") (pin "5") (pinfunction "5/PWM_5") (pintype "bidirectional"))
      (node (ref "IC9") (pin "13") (pinfunction "S3_13") (pintype "input"))
    )
    (net (code "118") (name "SCL") (class "Default")
      (node (ref "D2") (pin "A") (pinfunction "A_A") (pintype "passive"))
      (node (ref "D3") (pin "C") (pinfunction "C_C") (pintype "passive"))
      (node (ref "I2C") (pin "2") (pinfunction "2_2") (pintype "passive"))
      (node (ref "IC10") (pin "19/A5") (pinfunction "19/A5/T/SCL0_19/A5") (pintype "bidirectional"))
      (node (ref "JP1") (pin "P$2_SWITCH") (pinfunction "RIGHT_P$2_SWITCH") (pintype "bidirectional"))
      (node (ref "R49") (pin "1") (pinfunction "1_1") (pintype "passive"))
    )
    (net (code "119") (name "SDA") (class "Default")
      (node (ref "D4") (pin "C") (pinfunction "C_C") (pintype "passive"))
      (node (ref "D5") (pin "A") (pinfunction "A_A") (pintype "passive"))
      (node (ref "I2C") (pin "1") (pinfunction "1_1") (pintype "passive"))
      (node (ref "IC10") (pin "18/A4") (pinfunction "18/A4/T/SDA0_18/A4") (pintype "bidirectional"))
      (node (ref "JP1") (pin "P$1_TIP") (pinfunction "LEFT_P$1_TIP") (pintype "bidirectional"))
      (node (ref "R50") (pin "1") (pinfunction "1_1") (pintype "passive"))
    )
    (net (code "120") (name "W0") (class "Default")
      (node (ref "R17") (pin "2") (pinfunction "2_2") (pintype "passive"))
      (node (ref "R69") (pin "1") (pinfunction "1_1") (pintype "passive"))
      (node (ref "U$1") (pin "2") (pinfunction "2_2") (pintype "bidirectional"))
    )
    (net (code "121") (name "W1") (class "Default")
      (node (ref "R18") (pin "2") (pinfunction "2_2") (pintype "passive"))
      (node (ref "R53") (pin "1") (pinfunction "1_1") (pintype "passive"))
      (node (ref "U$2") (pin "2") (pinfunction "2_2") (pintype "bidirectional"))
    )
    (net (code "122") (name "W2") (class "Default")
      (node (ref "R19") (pin "2") (pinfunction "2_2") (pintype "passive"))
      (node (ref "R71") (pin "1") (pinfunction "1_1") (pintype "passive"))
      (node (ref "U$3") (pin "2") (pinfunction "2_2") (pintype "bidirectional"))
    )
    (net (code "123") (name "W3") (class "Default")
      (node (ref "R20") (pin "2") (pinfunction "2_2") (pintype "passive"))
      (node (ref "R55") (pin "1") (pinfunction "1_1") (pintype "passive"))
      (node (ref "U$4") (pin "2") (pinfunction "2_2") (pintype "bidirectional"))
    )
    (net (code "124") (name "W4") (class "Default")
      (node (ref "R21") (pin "2") (pinfunction "2_2") (pintype "passive"))
      (node (ref "R73") (pin "1") (pinfunction "1_1") (pintype "passive"))
      (node (ref "U$5") (pin "2") (pinfunction "2_2") (pintype "bidirectional"))
    )
    (net (code "125") (name "W5") (class "Default")
      (node (ref "R22") (pin "2") (pinfunction "2_2") (pintype "passive"))
      (node (ref "R57") (pin "1") (pinfunction "1_1") (pintype "passive"))
      (node (ref "U$6") (pin "2") (pinfunction "2_2") (pintype "bidirectional"))
    )
    (net (code "126") (name "W6") (class "Default")
      (node (ref "R23") (pin "2") (pinfunction "2_2") (pintype "passive"))
      (node (ref "R75") (pin "1") (pinfunction "1_1") (pintype "passive"))
      (node (ref "U$7") (pin "2") (pinfunction "2_2") (pintype "bidirectional"))
    )
    (net (code "127") (name "W7") (class "Default")
      (node (ref "R24") (pin "2") (pinfunction "2_2") (pintype "passive"))
      (node (ref "R59") (pin "1") (pinfunction "1_1") (pintype "passive"))
      (node (ref "U$8") (pin "2") (pinfunction "2_2") (pintype "bidirectional"))
    )
    (net (code "128") (name "W8") (class "Default")
      (node (ref "R25") (pin "2") (pinfunction "2_2") (pintype "passive"))
      (node (ref "R77") (pin "1") (pinfunction "1_1") (pintype "passive"))
      (node (ref "U$9") (pin "2") (pinfunction "2_2") (pintype "bidirectional"))
    )
    (net (code "129") (name "W9") (class "Default")
      (node (ref "R26") (pin "2") (pinfunction "2_2") (pintype "passive"))
      (node (ref "R61") (pin "1") (pinfunction "1_1") (pintype "passive"))
      (node (ref "U$10") (pin "2") (pinfunction "2_2") (pintype "bidirectional"))
    )
    (net (code "130") (name "W10") (class "Default")
      (node (ref "R27") (pin "2") (pinfunction "2_2") (pintype "passive"))
      (node (ref "R79") (pin "1") (pinfunction "1_1") (pintype "passive"))
      (node (ref "U$11") (pin "2") (pinfunction "2_2") (pintype "bidirectional"))
    )
    (net (code "131") (name "W11") (class "Default")
      (node (ref "R28") (pin "2") (pinfunction "2_2") (pintype "passive"))
      (node (ref "R63") (pin "1") (pinfunction "1_1") (pintype "passive"))
      (node (ref "U$12") (pin "2") (pinfunction "2_2") (pintype "bidirectional"))
    )
    (net (code "132") (name "W12") (class "Default")
      (node (ref "R29") (pin "2") (pinfunction "2_2") (pintype "passive"))
      (node (ref "R81") (pin "1") (pinfunction "1_1") (pintype "passive"))
      (node (ref "U$13") (pin "2") (pinfunction "2_2") (pintype "bidirectional"))
    )
    (net (code "133") (name "W13") (class "Default")
      (node (ref "R30") (pin "2") (pinfunction "2_2") (pintype "passive"))
      (node (ref "R65") (pin "1") (pinfunction "1_1") (pintype "passive"))
      (node (ref "U$14") (pin "2") (pinfunction "2_2") (pintype "bidirectional"))
    )
    (net (code "134") (name "W14") (class "Default")
      (node (ref "R31") (pin "2") (pinfunction "2_2") (pintype "passive"))
      (node (ref "R67") (pin "1") (pinfunction "1_1") (pintype "passive"))
      (node (ref "U$15") (pin "2") (pinfunction "2_2") (pintype "bidirectional"))
    )
    (net (code "135") (name "W15") (class "Default")
      (node (ref "R32") (pin "2") (pinfunction "2_2") (pintype "passive"))
      (node (ref "R51") (pin "1") (pinfunction "1_1") (pintype "passive"))
      (node (ref "U$16") (pin "2") (pinfunction "2_2") (pintype "bidirectional"))
    )
    (net (code "136") (name "unconnected-(IC10-0{slash}RX1{slash}T-Pad0)") (class "Default")
      (node (ref "IC10") (pin "0") (pinfunction "0/RX1/T_0") (pintype "bidirectional"))
    )
    (net (code "137") (name "unconnected-(IC10-3{slash}CAN-TX{slash}PWM-Pad3)") (class "Default")
      (node (ref "IC10") (pin "3") (pinfunction "3/CAN-TX/PWM_3") (pintype "bidirectional"))
    )
    (net (code "138") (name "unconnected-(IC10-4{slash}CAN-RX{slash}PWM-Pad4)") (class "Default")
      (node (ref "IC10") (pin "4") (pinfunction "4/CAN-RX/PWM_4") (pintype "bidirectional"))
    )
    (net (code "139") (name "unconnected-(IC10-9{slash}RX2{slash}PWM-Pad9)") (class "Default")
      (node (ref "IC10") (pin "9") (pinfunction "9/RX2/PWM_9") (pintype "bidirectional"))
    )
    (net (code "140") (name "unconnected-(IC10-10{slash}TX2{slash}PWM-Pad10)") (class "Default")
      (node (ref "IC10") (pin "10") (pinfunction "10/TX2/PWM_10") (pintype "bidirectional"))
    )
    (net (code "141") (name "unconnected-(IC10-11{slash}MOSI-Pad11)") (class "Default")
      (node (ref "IC10") (pin "11") (pinfunction "11/MOSI_11") (pintype "bidirectional"))
    )
    (net (code "142") (name "unconnected-(IC10-12{slash}MISO-Pad12)") (class "Default")
      (node (ref "IC10") (pin "12") (pinfunction "12/MISO_12") (pintype "bidirectional"))
    )
    (net (code "143") (name "unconnected-(IC10-13{slash}SCK{slash}LED-Pad13)") (class "Default")
      (node (ref "IC10") (pin "13") (pinfunction "13/SCK/LED_13") (pintype "bidirectional"))
    )
    (net (code "144") (name "unconnected-(IC10-15{slash}A1{slash}T-Pad15{slash}A1)") (class "Default")
      (node (ref "IC10") (pin "15/A1") (pinfunction "15/A1/T_15/A1") (pintype "bidirectional"))
    )
    (net (code "145") (name "unconnected-(IC10-16{slash}A2{slash}T-Pad16{slash}A2)") (class "Default")
      (node (ref "IC10") (pin "16/A2") (pinfunction "16/A2/T_16/A2") (pintype "bidirectional"))
    )
    (net (code "146") (name "unconnected-(IC10-17{slash}A3{slash}T-Pad17{slash}A3)") (class "Default")
      (node (ref "IC10") (pin "17/A3") (pinfunction "17/A3/T_17/A3") (pintype "bidirectional"))
    )
    (net (code "147") (name "unconnected-(IC10-20{slash}A6{slash}PWM-Pad20{slash}A6)") (class "Default")
      (node (ref "IC10") (pin "20/A6") (pinfunction "20/A6/PWM_20/A6") (pintype "bidirectional"))
    )
    (net (code "148") (name "unconnected-(IC10-21{slash}A7{slash}PWM-Pad21{slash}A7)") (class "Default")
      (node (ref "IC10") (pin "21/A7") (pinfunction "21/A7/PWM_21/A7") (pintype "bidirectional"))
    )
    (net (code "149") (name "unconnected-(IC10-22{slash}A8{slash}T{slash}PWM-Pad22{slash}A8)") (class "Default")
      (node (ref "IC10") (pin "22/A8") (pinfunction "22/A8/T/PWM_22/A8") (pintype "bidirectional"))
    )
    (net (code "150") (name "unconnected-(IC10-23{slash}A9{slash}T{slash}PWM-Pad23{slash}A9)") (class "Default")
      (node (ref "IC10") (pin "23/A9") (pinfunction "23/A9/T/PWM_23/A9") (pintype "bidirectional"))
    )
    (net (code "151") (name "unconnected-(IC10-Pad2)") (class "Default")
      (node (ref "IC10") (pin "2") (pinfunction "2_2") (pintype "bidirectional"))
    )
    (net (code "152") (name "unconnected-(J1-SWITCH-PadP$2_SWITCH)") (class "Default")
      (node (ref "J1") (pin "P$2_SWITCH") (pinfunction "SWITCH_P$2_SWITCH") (pintype "passive"))
    )
    (net (code "153") (name "unconnected-(J2-SWITCH-PadP$2_SWITCH)") (class "Default")
      (node (ref "J2") (pin "P$2_SWITCH") (pinfunction "SWITCH_P$2_SWITCH") (pintype "passive"))
    )
    (net (code "154") (name "unconnected-(J3-SWITCH-PadP$2_SWITCH)") (class "Default")
      (node (ref "J3") (pin "P$2_SWITCH") (pinfunction "SWITCH_P$2_SWITCH") (pintype "passive"))
    )
    (net (code "155") (name "unconnected-(J4-SWITCH-PadP$2_SWITCH)") (class "Default")
      (node (ref "J4") (pin "P$2_SWITCH") (pinfunction "SWITCH_P$2_SWITCH") (pintype "passive"))
    )
    (net (code "156") (name "unconnected-(J5-SWITCH-PadP$2_SWITCH)") (class "Default")
      (node (ref "J5") (pin "P$2_SWITCH") (pinfunction "SWITCH_P$2_SWITCH") (pintype "passive"))
    )
    (net (code "157") (name "unconnected-(J6-SWITCH-PadP$2_SWITCH)") (class "Default")
      (node (ref "J6") (pin "P$2_SWITCH") (pinfunction "SWITCH_P$2_SWITCH") (pintype "passive"))
    )
    (net (code "158") (name "unconnected-(J7-SWITCH-PadP$2_SWITCH)") (class "Default")
      (node (ref "J7") (pin "P$2_SWITCH") (pinfunction "SWITCH_P$2_SWITCH") (pintype "passive"))
    )
    (net (code "159") (name "unconnected-(J8-SWITCH-PadP$2_SWITCH)") (class "Default")
      (node (ref "J8") (pin "P$2_SWITCH") (pinfunction "SWITCH_P$2_SWITCH") (pintype "passive"))
    )
    (net (code "160") (name "unconnected-(J9-SWITCH-PadP$2_SWITCH)") (class "Default")
      (node (ref "J9") (pin "P$2_SWITCH") (pinfunction "SWITCH_P$2_SWITCH") (pintype "passive"))
    )
    (net (code "161") (name "unconnected-(J10-SWITCH-PadP$2_SWITCH)") (class "Default")
      (node (ref "J10") (pin "P$2_SWITCH") (pinfunction "SWITCH_P$2_SWITCH") (pintype "passive"))
    )
    (net (code "162") (name "unconnected-(J11-SWITCH-PadP$2_SWITCH)") (class "Default")
      (node (ref "J11") (pin "P$2_SWITCH") (pinfunction "SWITCH_P$2_SWITCH") (pintype "passive"))
    )
    (net (code "163") (name "unconnected-(J12-SWITCH-PadP$2_SWITCH)") (class "Default")
      (node (ref "J12") (pin "P$2_SWITCH") (pinfunction "SWITCH_P$2_SWITCH") (pintype "passive"))
    )
    (net (code "164") (name "unconnected-(J13-SWITCH-PadP$2_SWITCH)") (class "Default")
      (node (ref "J13") (pin "P$2_SWITCH") (pinfunction "SWITCH_P$2_SWITCH") (pintype "passive"))
    )
    (net (code "165") (name "unconnected-(J14-SWITCH-PadP$2_SWITCH)") (class "Default")
      (node (ref "J14") (pin "P$2_SWITCH") (pinfunction "SWITCH_P$2_SWITCH") (pintype "passive"))
    )
    (net (code "166") (name "unconnected-(J15-SWITCH-PadP$2_SWITCH)") (class "Default")
      (node (ref "J15") (pin "P$2_SWITCH") (pinfunction "SWITCH_P$2_SWITCH") (pintype "passive"))
    )
    (net (code "167") (name "unconnected-(J16-SWITCH-PadP$2_SWITCH)") (class "Default")
      (node (ref "J16") (pin "P$2_SWITCH") (pinfunction "SWITCH_P$2_SWITCH") (pintype "passive"))
    )
    (net (code "168") (name "unconnected-(S101-3-PadP1-TB)") (class "Default")
      (node (ref "S101") (pin "P1-TB") (pinfunction "3_P1-TB") (pintype "bidirectional"))
    )
    (net (code "169") (name "unconnected-(SV100-Pad1)") (class "Default")
      (node (ref "SV100") (pin "1") (pinfunction "1_1") (pintype "passive"))
    )
    (net (code "170") (name "unconnected-(SV100-Pad2)") (class "Default")
      (node (ref "SV100") (pin "2") (pinfunction "2_2") (pintype "passive"))
    )
  )
)
